# ComputeCalculator.net
KiCad netlist of a schematic drawn in EAGLE
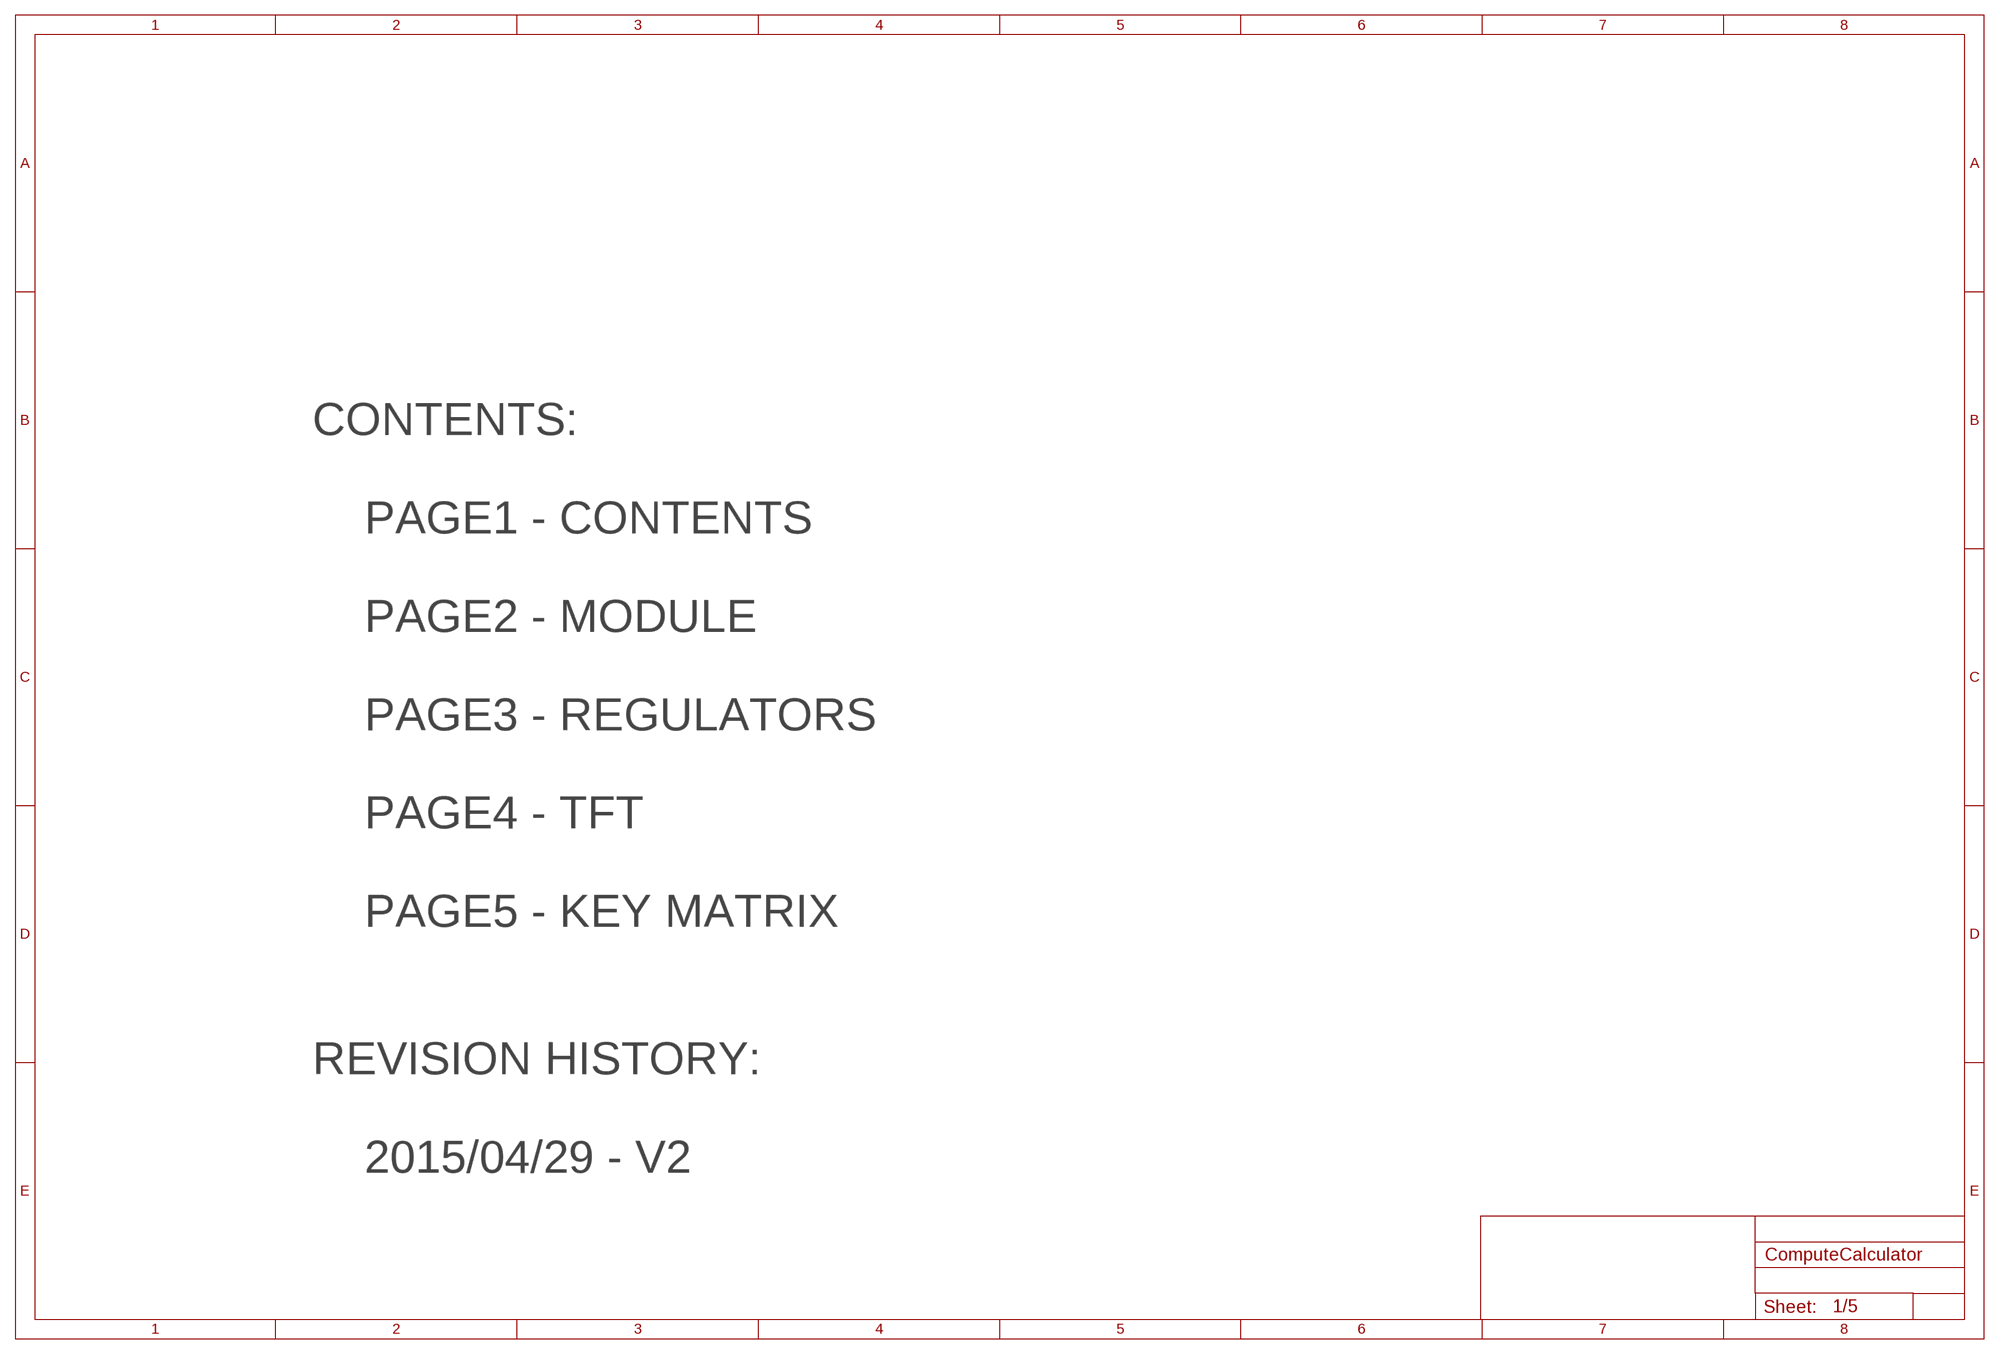
[diagram p0: schematic, sheet 1]
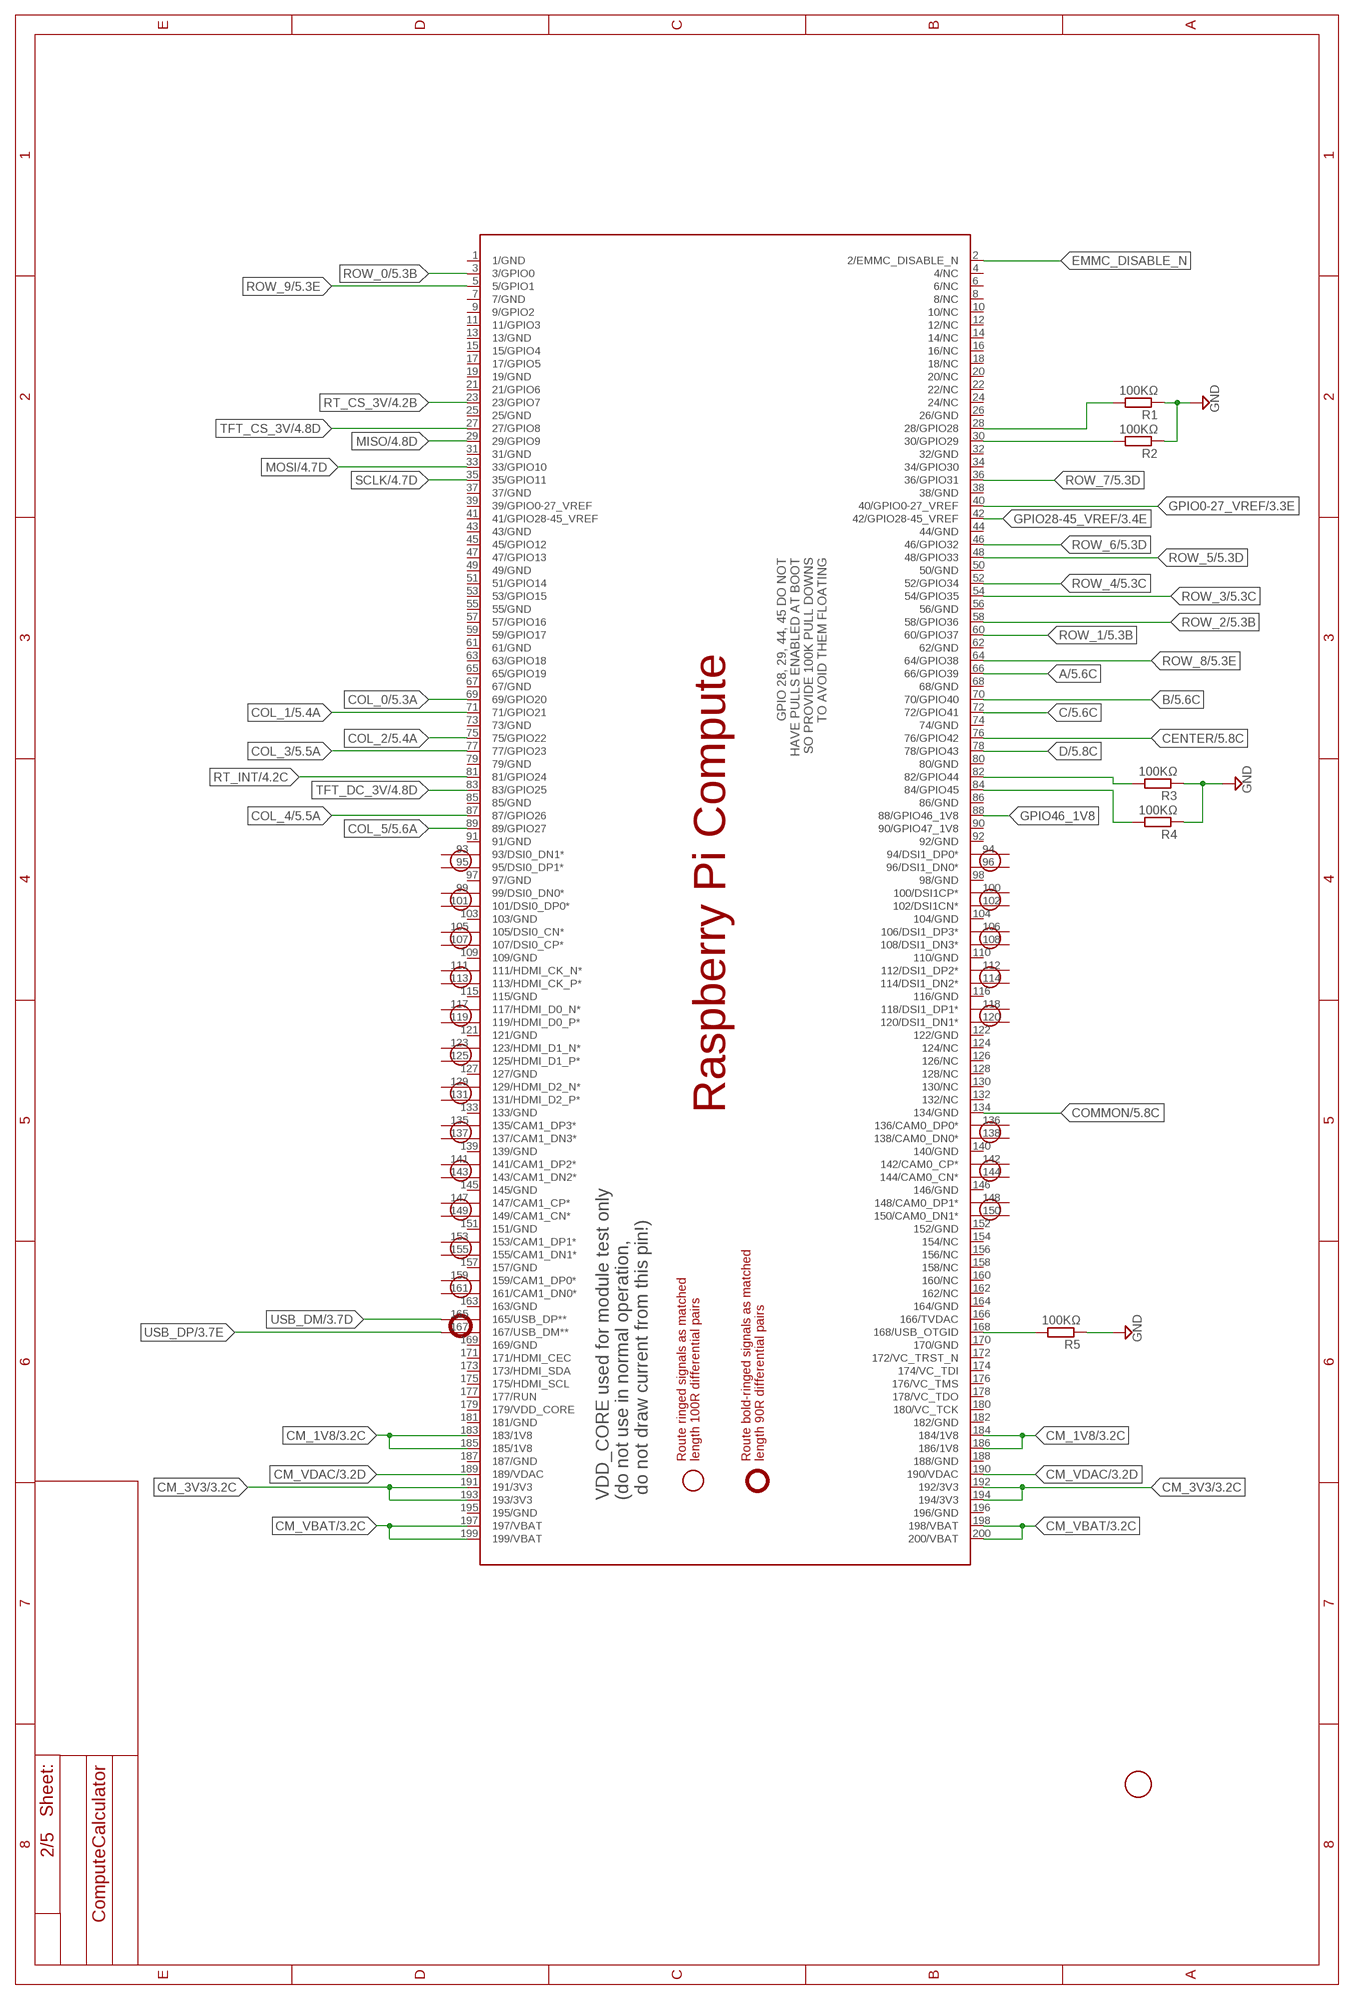
[diagram p1: schematic, sheet 2]
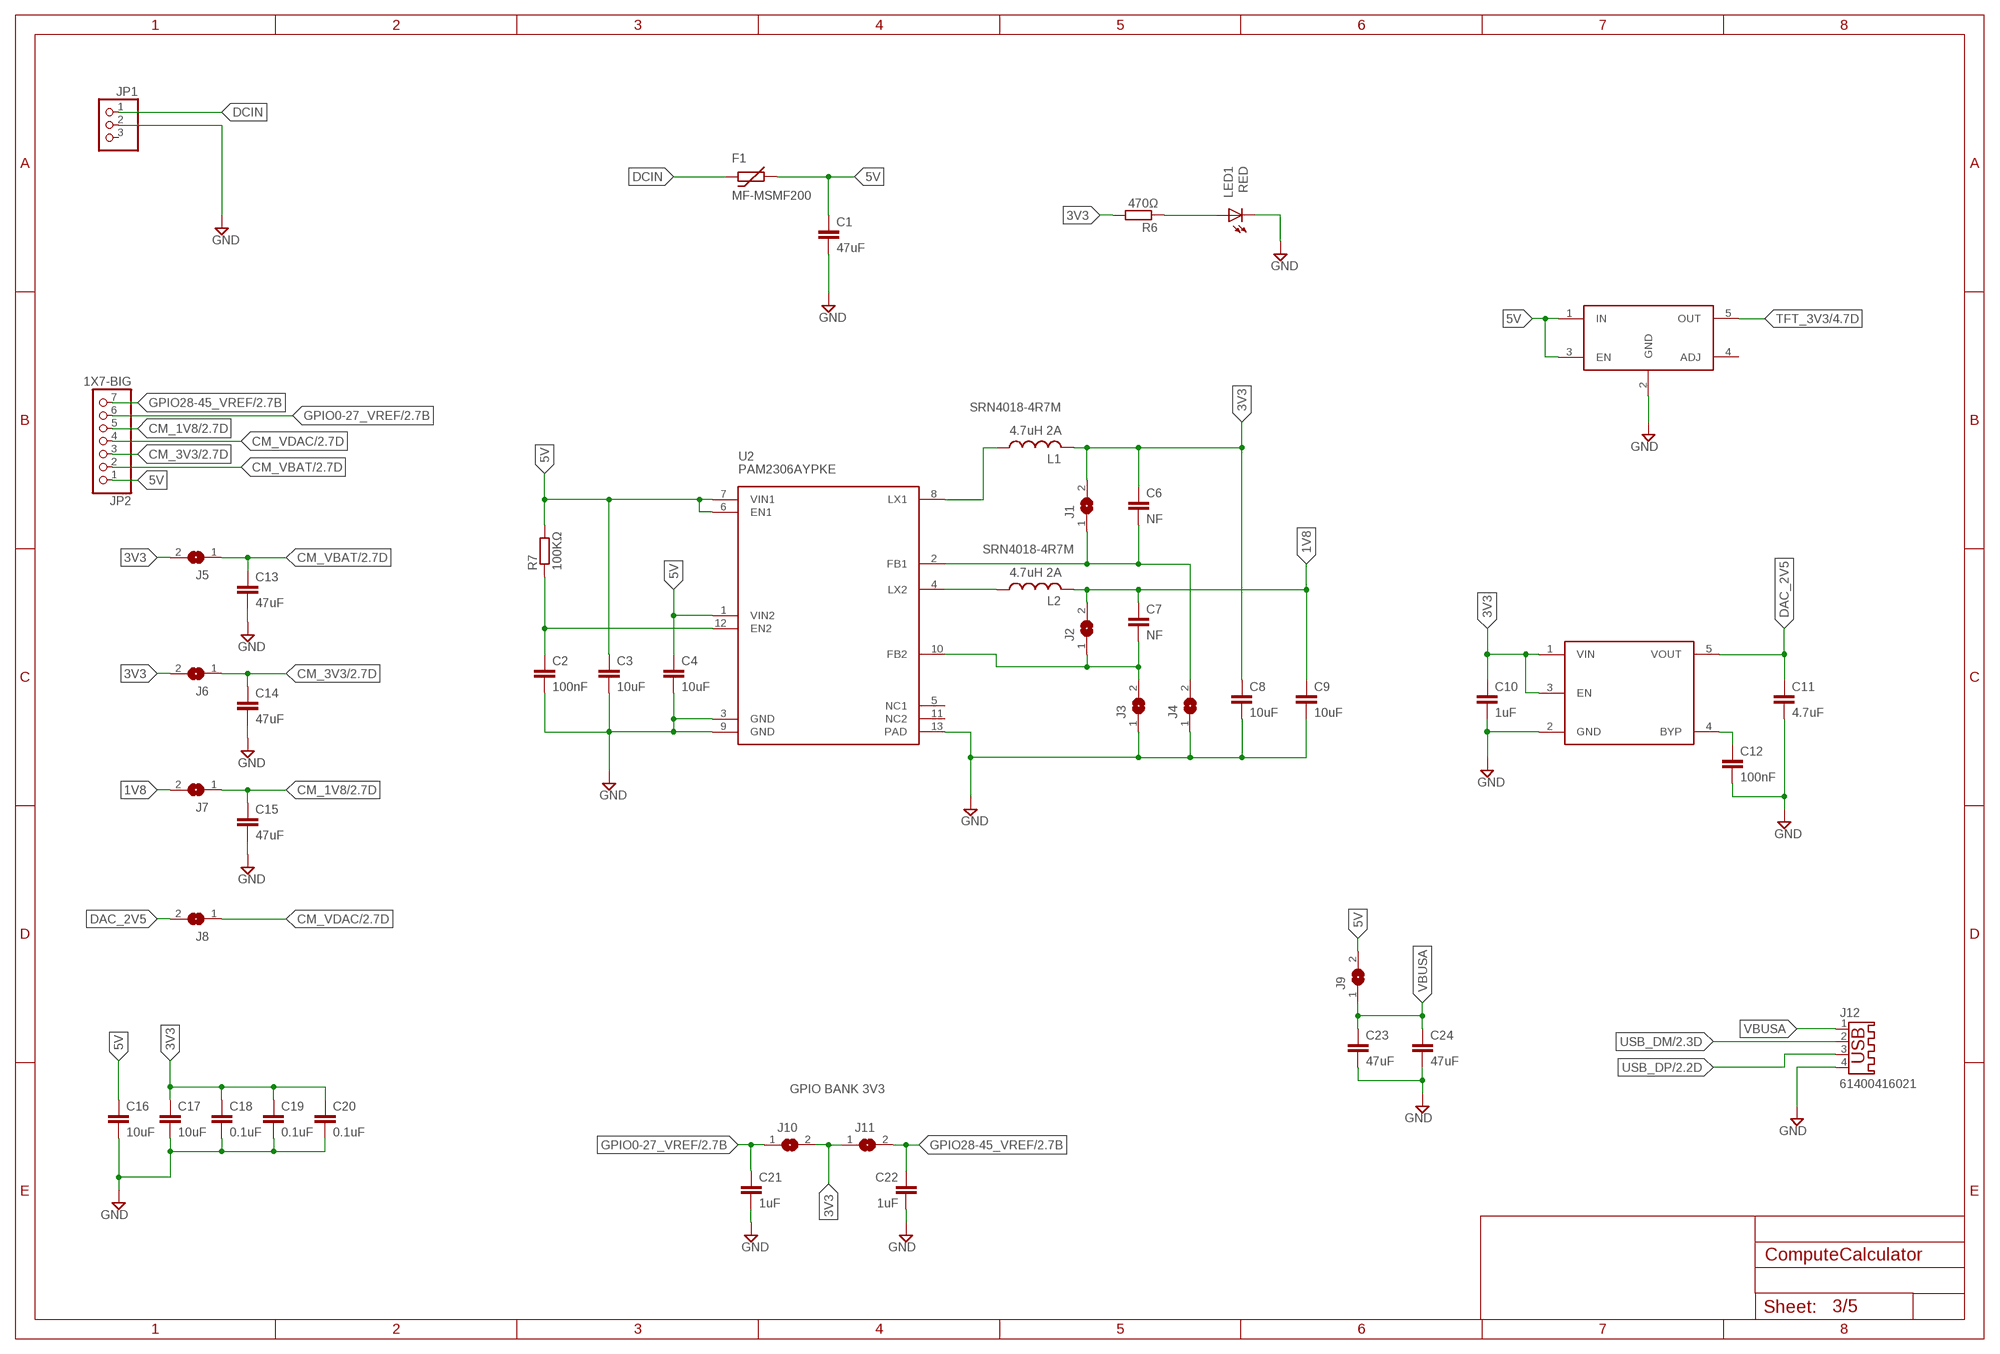
[diagram p2: schematic, sheet 3]
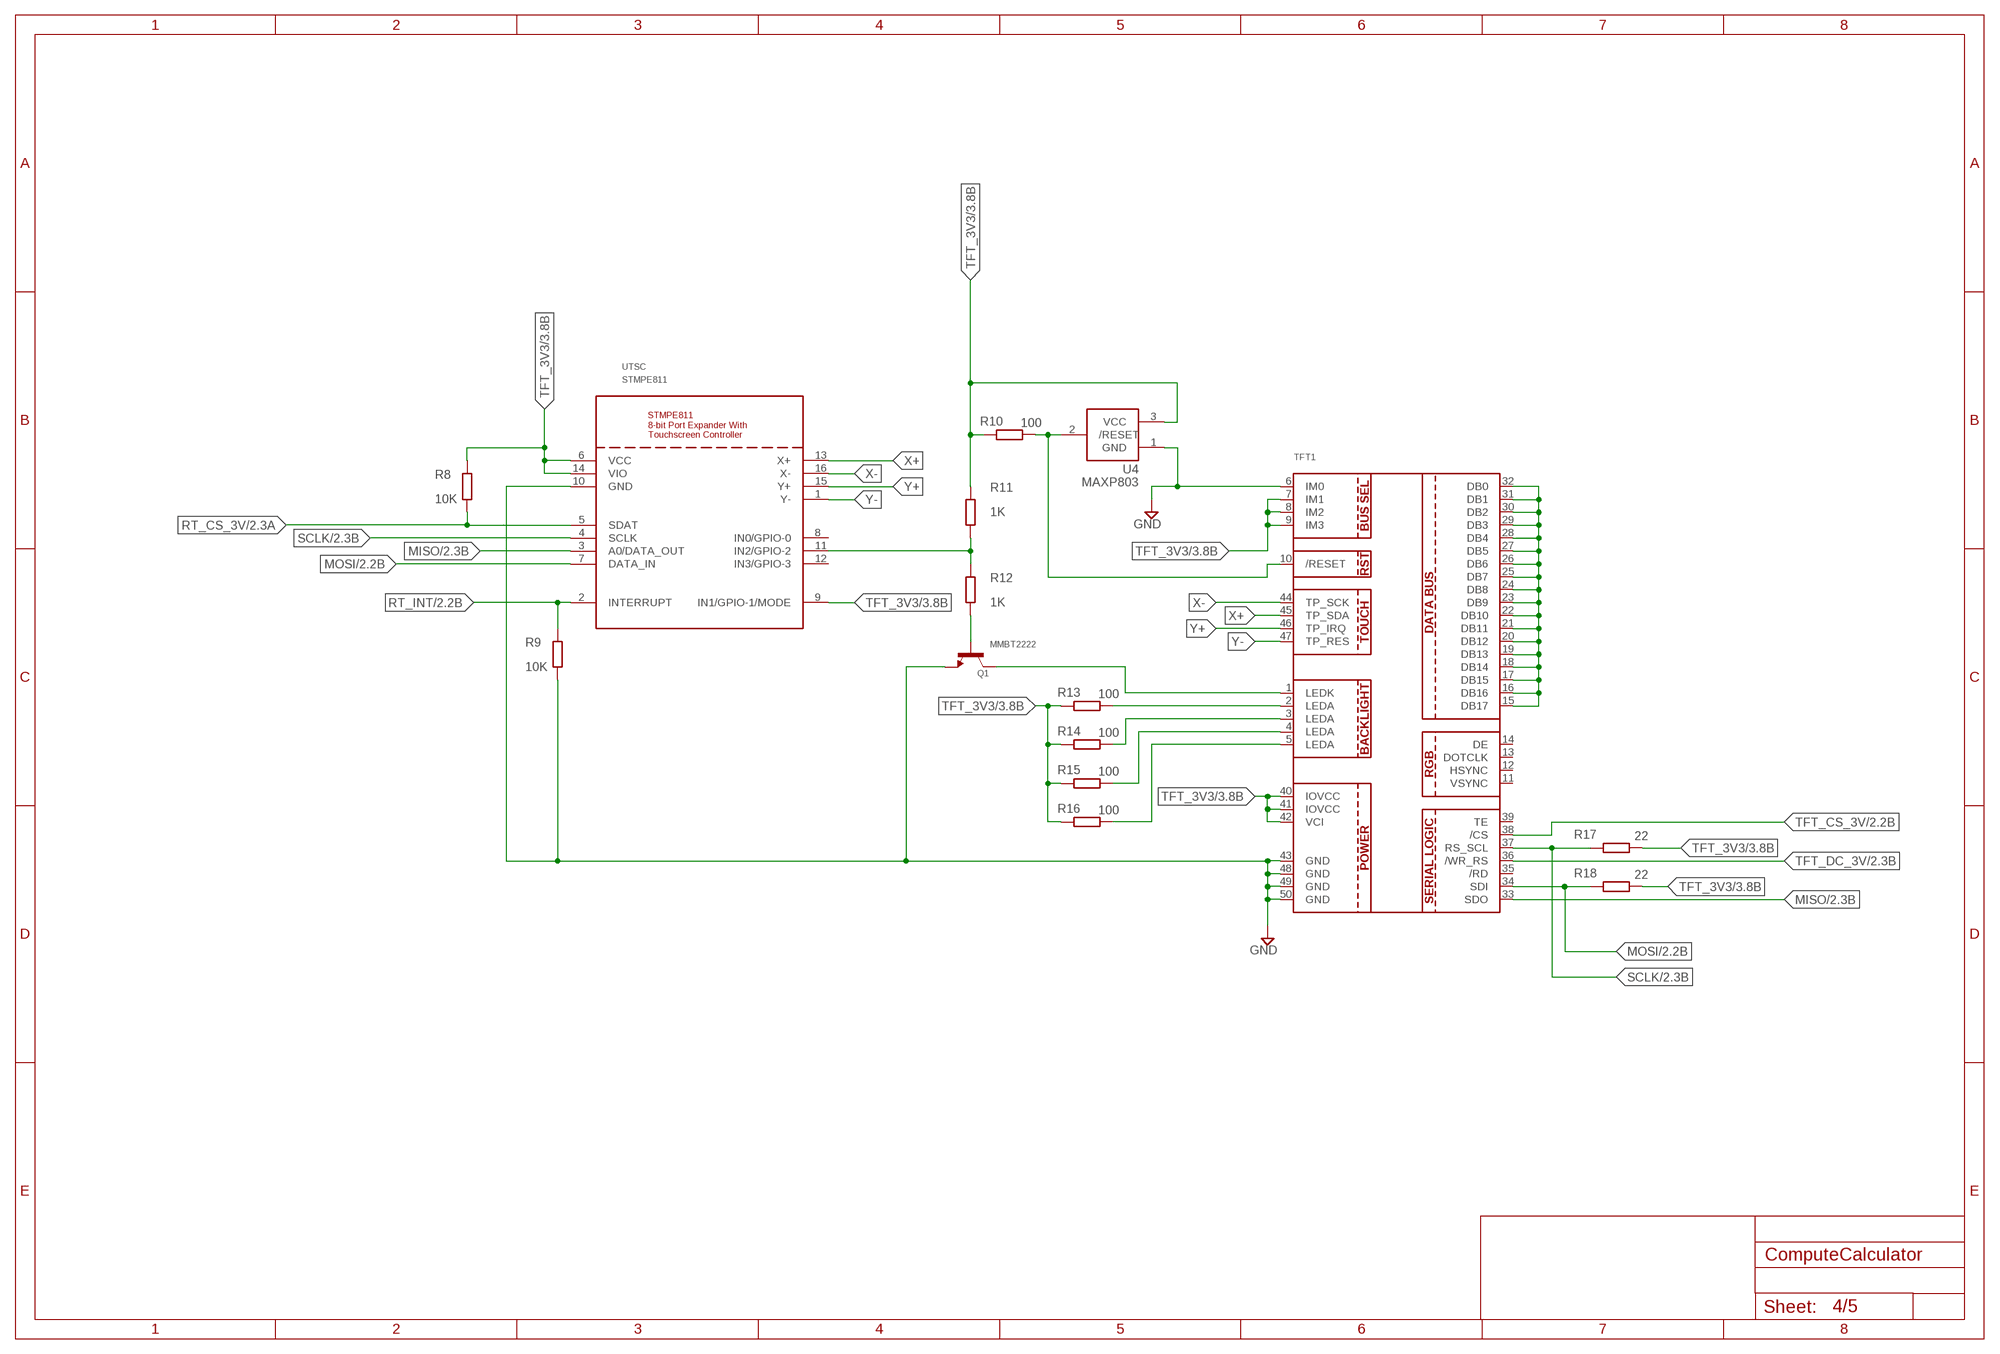
[diagram p3: schematic, sheet 4]
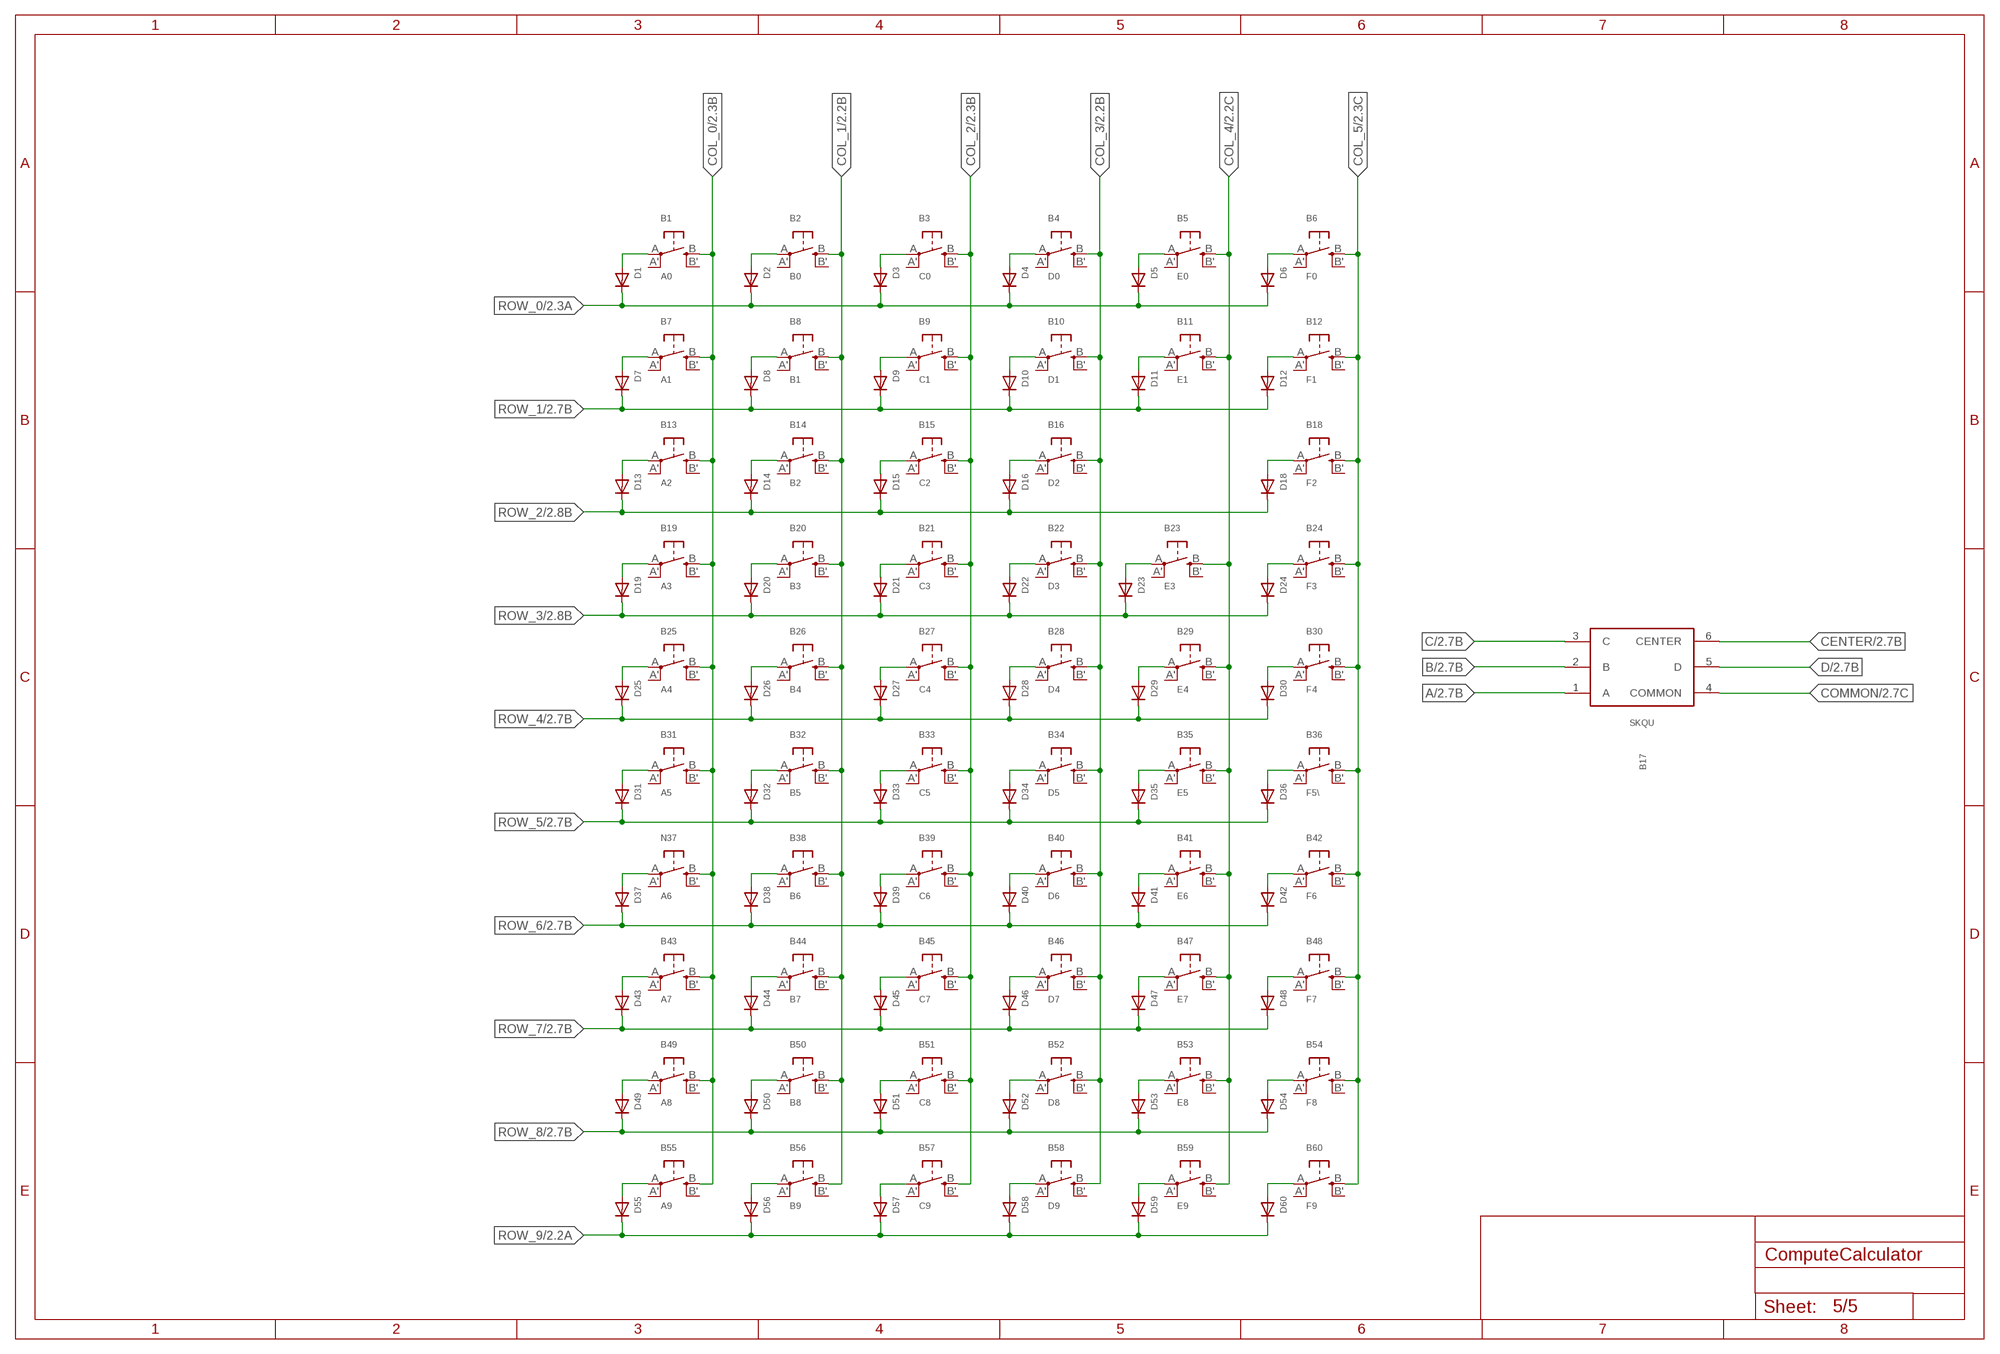
[diagram p4: schematic, sheet 5]

(export (version "E")
  (design (tool "Eeschema 10.0.6"))
  (components
    (comp (ref "C1")
      (value "47uF")
      (footprint "eagle-import:C0603")
      (libsource (lib "eagle-import") (part "CAPACITOR"))
    )
    (comp (ref "C2")
      (value "100nF")
      (footprint "eagle-import:C1206")
      (libsource (lib "eagle-import") (part "C-EUC1206"))
    )
    (comp (ref "C3")
      (value "10uF")
      (footprint "eagle-import:C1206")
      (libsource (lib "eagle-import") (part "C-EUC1206"))
    )
    (comp (ref "C4")
      (value "10uF")
      (footprint "eagle-import:C1206")
      (libsource (lib "eagle-import") (part "C-EUC1206"))
    )
    (comp (ref "C6")
      (value "NF")
      (footprint "eagle-import:C1206")
      (libsource (lib "eagle-import") (part "C-EUC1206"))
    )
    (comp (ref "C7")
      (value "NF")
      (footprint "eagle-import:C1206")
      (libsource (lib "eagle-import") (part "C-EUC1206"))
    )
    (comp (ref "C8")
      (value "10uF")
      (footprint "eagle-import:C1206")
      (libsource (lib "eagle-import") (part "C-EUC1206"))
    )
    (comp (ref "C9")
      (value "10uF")
      (footprint "eagle-import:C1206")
      (libsource (lib "eagle-import") (part "C-EUC1206"))
    )
    (comp (ref "C10")
      (value "1uF")
      (footprint "eagle-import:C1206")
      (libsource (lib "eagle-import") (part "C-EUC1206"))
    )
    (comp (ref "C11")
      (value "4.7uF")
      (footprint "eagle-import:C1206")
      (libsource (lib "eagle-import") (part "C-EUC1206"))
    )
    (comp (ref "C12")
      (value "100nF")
      (footprint "eagle-import:C1206")
      (libsource (lib "eagle-import") (part "C-EUC1206"))
    )
    (comp (ref "C13")
      (value "47uF")
      (footprint "eagle-import:C1206")
      (libsource (lib "eagle-import") (part "C-EUC1206"))
    )
    (comp (ref "C14")
      (value "47uF")
      (footprint "eagle-import:C1206")
      (libsource (lib "eagle-import") (part "C-EUC1206"))
    )
    (comp (ref "C15")
      (value "47uF")
      (footprint "eagle-import:C1206")
      (libsource (lib "eagle-import") (part "C-EUC1206"))
    )
    (comp (ref "C16")
      (value "10uF")
      (footprint "eagle-import:C1206")
      (libsource (lib "eagle-import") (part "C-EUC1206"))
    )
    (comp (ref "C17")
      (value "10uF")
      (footprint "eagle-import:C1206")
      (libsource (lib "eagle-import") (part "C-EUC1206"))
    )
    (comp (ref "C18")
      (value "0.1uF")
      (footprint "eagle-import:C1206")
      (libsource (lib "eagle-import") (part "C-EUC1206"))
    )
    (comp (ref "C19")
      (value "0.1uF")
      (footprint "eagle-import:C1206")
      (libsource (lib "eagle-import") (part "C-EUC1206"))
    )
    (comp (ref "C20")
      (value "0.1uF")
      (footprint "eagle-import:C1206")
      (libsource (lib "eagle-import") (part "C-EUC1206"))
    )
    (comp (ref "C21")
      (value "1uF")
      (footprint "eagle-import:C1206")
      (libsource (lib "eagle-import") (part "C-EUC1206"))
    )
    (comp (ref "C22")
      (value "1uF")
      (footprint "eagle-import:C1206")
      (libsource (lib "eagle-import") (part "C-EUC1206"))
    )
    (comp (ref "C23")
      (value "47uF")
      (footprint "eagle-import:C1206")
      (libsource (lib "eagle-import") (part "C-EUC1206"))
    )
    (comp (ref "C24")
      (value "47uF")
      (footprint "eagle-import:C1206")
      (libsource (lib "eagle-import") (part "C-EUC1206"))
    )
    (comp (ref "F1")
      (value "MF-MSMF200")
      (footprint "eagle-import:MF-MSMF200")
      (libsource (lib "eagle-import") (part "MF-MSMF200"))
    )
    (comp (ref "J1")
      (value "JUMPER")
      (footprint "eagle-import:SJW")
      (libsource (lib "eagle-import") (part "JUMPER"))
    )
    (comp (ref "J2")
      (value "JUMPER")
      (footprint "eagle-import:SJW")
      (libsource (lib "eagle-import") (part "JUMPER"))
    )
    (comp (ref "J3")
      (value "JUMPER")
      (footprint "eagle-import:SJW")
      (libsource (lib "eagle-import") (part "JUMPER"))
    )
    (comp (ref "J4")
      (value "JUMPER")
      (footprint "eagle-import:SJW")
      (libsource (lib "eagle-import") (part "JUMPER"))
    )
    (comp (ref "J5")
      (value "JUMPER")
      (footprint "eagle-import:SJW")
      (libsource (lib "eagle-import") (part "JUMPER"))
    )
    (comp (ref "J6")
      (value "JUMPER")
      (footprint "eagle-import:SJW")
      (libsource (lib "eagle-import") (part "JUMPER"))
    )
    (comp (ref "J7")
      (value "JUMPER")
      (footprint "eagle-import:SJW")
      (libsource (lib "eagle-import") (part "JUMPER"))
    )
    (comp (ref "J8")
      (value "JUMPER")
      (footprint "eagle-import:SJW")
      (libsource (lib "eagle-import") (part "JUMPER"))
    )
    (comp (ref "J9")
      (value "JUMPER")
      (footprint "eagle-import:SJW")
      (libsource (lib "eagle-import") (part "JUMPER"))
    )
    (comp (ref "J10")
      (value "JUMPER")
      (footprint "eagle-import:SJW")
      (libsource (lib "eagle-import") (part "JUMPER"))
    )
    (comp (ref "J11")
      (value "JUMPER")
      (footprint "eagle-import:SJW")
      (libsource (lib "eagle-import") (part "JUMPER"))
    )
    (comp (ref "J12")
      (value "61400416021")
      (footprint "eagle-import:USB-A003")
      (libsource (lib "eagle-import") (part "USB-A003"))
    )
    (comp (ref "JP1")
      (value "PINHD-1X3")
      (footprint "eagle-import:1X03")
      (libsource (lib "eagle-import") (part "PINHD-1X3"))
    )
    (comp (ref "JP2")
      (value "1X7-BIG")
      (footprint "eagle-import:1X7-BIG")
      (libsource (lib "eagle-import") (part "1X7-BIG"))
    )
    (comp (ref "L1")
      (value "SRN4018-4R7M")
      (footprint "eagle-import:POWER-CHOKE_WE-TPC")
      (libsource (lib "eagle-import") (part "L-USWE-TPC"))
    )
    (comp (ref "L2")
      (value "SRN4018-4R7M")
      (footprint "eagle-import:POWER-CHOKE_WE-TPC")
      (libsource (lib "eagle-import") (part "L-USWE-TPC"))
    )
    (comp (ref "LED1")
      (value "RED")
      (footprint "eagle-import:CHIP-LED0805")
      (libsource (lib "eagle-import") (part "LEDCHIP-LED0805"))
    )
    (comp (ref "R6")
      (value "470Ω")
      (footprint "eagle-import:M1206")
      (libsource (lib "eagle-import") (part "R-EU_M1206"))
    )
    (comp (ref "R7")
      (value "100KΩ")
      (footprint "eagle-import:M1206")
      (libsource (lib "eagle-import") (part "R-EU_M1206"))
    )
    (comp (ref "U1")
      (value "MIC5225")
      (footprint "eagle-import:SOT-25")
      (libsource (lib "eagle-import") (part "MIC5225"))
    )
    (comp (ref "U2")
      (value "PAM2306AYPKE")
      (footprint "eagle-import:WDFN_12L")
      (libsource (lib "eagle-import") (part "PAM2306AYPKE"))
    )
    (comp (ref "U3")
      (value "AP7115-25SEG")
      (footprint "eagle-import:SOT-25")
      (libsource (lib "eagle-import") (part "AP7115-25SEG"))
    )
    (comp (ref "Q1")
      (value "MMBT2222")
      (footprint "eagle-import:SOT23-WIDE")
      (libsource (lib "eagle-import") (part "TRANSISTOR_NPNWIDE"))
    )
    (comp (ref "R8")
      (value "10K")
      (footprint "eagle-import:M1206")
      (libsource (lib "eagle-import") (part "R-EU_M1206"))
    )
    (comp (ref "R9")
      (value "10K")
      (footprint "eagle-import:M1206")
      (libsource (lib "eagle-import") (part "R-EU_M1206"))
    )
    (comp (ref "R10")
      (value "100")
      (footprint "eagle-import:M1206")
      (libsource (lib "eagle-import") (part "R-EU_M1206"))
    )
    (comp (ref "R11")
      (value "1K")
      (footprint "eagle-import:M1206")
      (libsource (lib "eagle-import") (part "R-EU_M1206"))
    )
    (comp (ref "R12")
      (value "1K")
      (footprint "eagle-import:M1206")
      (libsource (lib "eagle-import") (part "R-EU_M1206"))
    )
    (comp (ref "R13")
      (value "100")
      (footprint "eagle-import:M1206")
      (libsource (lib "eagle-import") (part "R-EU_M1206"))
    )
    (comp (ref "R14")
      (value "100")
      (footprint "eagle-import:M1206")
      (libsource (lib "eagle-import") (part "R-EU_M1206"))
    )
    (comp (ref "R15")
      (value "100")
      (footprint "eagle-import:M1206")
      (libsource (lib "eagle-import") (part "R-EU_M1206"))
    )
    (comp (ref "R16")
      (value "100")
      (footprint "eagle-import:M1206")
      (libsource (lib "eagle-import") (part "R-EU_M1206"))
    )
    (comp (ref "R17")
      (value "22")
      (footprint "eagle-import:M1206")
      (libsource (lib "eagle-import") (part "R-EU_M1206"))
    )
    (comp (ref "R18")
      (value "22")
      (footprint "eagle-import:M1206")
      (libsource (lib "eagle-import") (part "R-EU_M1206"))
    )
    (comp (ref "TFT1")
      (value "DISP_LCD_CTP28_DATASHEET")
      (footprint "eagle-import:TFT_CTP28")
      (libsource (lib "eagle-import") (part "DISP_LCD_CTP28_DATASHEET"))
    )
    (comp (ref "U4")
      (value "MAXP803")
      (footprint "eagle-import:SOT23")
      (libsource (lib "eagle-import") (part "AXP083-SAG"))
    )
    (comp (ref "UTSC")
      (value "STMPE811")
      (footprint "eagle-import:QFN16L")
      (libsource (lib "eagle-import") (part "STMPE811"))
    )
    (comp (ref "$$PCB100")
      (value "RPI_COMPUTE")
      (footprint "eagle-import:RPI_COMPUTE")
      (libsource (lib "eagle-import") (part "RPI_COMPUTE"))
    )
    (comp (ref "$$U$1")
      (value "FIDUCIAL")
      (footprint "eagle-import:FIDUCIAL_1MM")
      (libsource (lib "eagle-import") (part "FIDUCIAL"))
    )
    (comp (ref "R1")
      (value "100KΩ")
      (footprint "eagle-import:M1206")
      (libsource (lib "eagle-import") (part "R-EU_M1206"))
    )
    (comp (ref "R2")
      (value "100KΩ")
      (footprint "eagle-import:M1206")
      (libsource (lib "eagle-import") (part "R-EU_M1206"))
    )
    (comp (ref "R3")
      (value "100KΩ")
      (footprint "eagle-import:M1206")
      (libsource (lib "eagle-import") (part "R-EU_M1206"))
    )
    (comp (ref "R4")
      (value "100KΩ")
      (footprint "eagle-import:M1206")
      (libsource (lib "eagle-import") (part "R-EU_M1206"))
    )
    (comp (ref "R5")
      (value "100KΩ")
      (footprint "eagle-import:M1206")
      (libsource (lib "eagle-import") (part "R-EU_M1206"))
    )
    (comp (ref "B1")
      (value "A0")
      (footprint "eagle-import:EVQ-Q2")
      (libsource (lib "eagle-import") (part "SWITCH_TACT_SMT"))
    )
    (comp (ref "B2")
      (value "B0")
      (footprint "eagle-import:EVQ-Q2")
      (libsource (lib "eagle-import") (part "SWITCH_TACT_SMT"))
    )
    (comp (ref "B3")
      (value "C0")
      (footprint "eagle-import:EVQ-Q2")
      (libsource (lib "eagle-import") (part "SWITCH_TACT_SMT"))
    )
    (comp (ref "B4")
      (value "D0")
      (footprint "eagle-import:EVQ-Q2")
      (libsource (lib "eagle-import") (part "SWITCH_TACT_SMT"))
    )
    (comp (ref "B5")
      (value "E0")
      (footprint "eagle-import:EVQ-Q2")
      (libsource (lib "eagle-import") (part "SWITCH_TACT_SMT"))
    )
    (comp (ref "B6")
      (value "F0")
      (footprint "eagle-import:EVQ-Q2")
      (libsource (lib "eagle-import") (part "SWITCH_TACT_SMT"))
    )
    (comp (ref "B7")
      (value "A1")
      (footprint "eagle-import:EVQ-Q2")
      (libsource (lib "eagle-import") (part "SWITCH_TACT_SMT"))
    )
    (comp (ref "B8")
      (value "B1")
      (footprint "eagle-import:EVQ-Q2")
      (libsource (lib "eagle-import") (part "SWITCH_TACT_SMT"))
    )
    (comp (ref "B9")
      (value "C1")
      (footprint "eagle-import:EVQ-Q2")
      (libsource (lib "eagle-import") (part "SWITCH_TACT_SMT"))
    )
    (comp (ref "B10")
      (value "D1")
      (footprint "eagle-import:EVQ-Q2")
      (libsource (lib "eagle-import") (part "SWITCH_TACT_SMT"))
    )
    (comp (ref "B11")
      (value "E1")
      (footprint "eagle-import:EVQ-Q2")
      (libsource (lib "eagle-import") (part "SWITCH_TACT_SMT"))
    )
    (comp (ref "B12")
      (value "F1")
      (footprint "eagle-import:EVQ-Q2")
      (libsource (lib "eagle-import") (part "SWITCH_TACT_SMT"))
    )
    (comp (ref "B13")
      (value "A2")
      (footprint "eagle-import:EVQ-Q2")
      (libsource (lib "eagle-import") (part "SWITCH_TACT_SMT"))
    )
    (comp (ref "B14")
      (value "B2")
      (footprint "eagle-import:EVQ-Q2")
      (libsource (lib "eagle-import") (part "SWITCH_TACT_SMT"))
    )
    (comp (ref "B15")
      (value "C2")
      (footprint "eagle-import:EVQ-Q2")
      (libsource (lib "eagle-import") (part "SWITCH_TACT_SMT"))
    )
    (comp (ref "B16")
      (value "D2")
      (footprint "eagle-import:EVQ-Q2")
      (libsource (lib "eagle-import") (part "SWITCH_TACT_SMT"))
    )
    (comp (ref "B17")
      (value "SKQU")
      (footprint "eagle-import:SKQU")
      (libsource (lib "eagle-import") (part "SKQU"))
    )
    (comp (ref "B18")
      (value "F2")
      (footprint "eagle-import:EVQ-Q2")
      (libsource (lib "eagle-import") (part "SWITCH_TACT_SMT"))
    )
    (comp (ref "B19")
      (value "A3")
      (footprint "eagle-import:EVQ-Q2")
      (libsource (lib "eagle-import") (part "SWITCH_TACT_SMT"))
    )
    (comp (ref "B20")
      (value "B3")
      (footprint "eagle-import:EVQ-Q2")
      (libsource (lib "eagle-import") (part "SWITCH_TACT_SMT"))
    )
    (comp (ref "B21")
      (value "C3")
      (footprint "eagle-import:EVQ-Q2")
      (libsource (lib "eagle-import") (part "SWITCH_TACT_SMT"))
    )
    (comp (ref "B22")
      (value "D3")
      (footprint "eagle-import:EVQ-Q2")
      (libsource (lib "eagle-import") (part "SWITCH_TACT_SMT"))
    )
    (comp (ref "B23")
      (value "E3")
      (footprint "eagle-import:EVQ-Q2")
      (libsource (lib "eagle-import") (part "SWITCH_TACT_SMT"))
    )
    (comp (ref "B24")
      (value "F3")
      (footprint "eagle-import:EVQ-Q2")
      (libsource (lib "eagle-import") (part "SWITCH_TACT_SMT"))
    )
    (comp (ref "B25")
      (value "A4")
      (footprint "eagle-import:EVQ-Q2")
      (libsource (lib "eagle-import") (part "SWITCH_TACT_SMT"))
    )
    (comp (ref "B26")
      (value "B4")
      (footprint "eagle-import:EVQ-Q2")
      (libsource (lib "eagle-import") (part "SWITCH_TACT_SMT"))
    )
    (comp (ref "B27")
      (value "C4")
      (footprint "eagle-import:EVQ-Q2")
      (libsource (lib "eagle-import") (part "SWITCH_TACT_SMT"))
    )
    (comp (ref "B28")
      (value "D4")
      (footprint "eagle-import:EVQ-Q2")
      (libsource (lib "eagle-import") (part "SWITCH_TACT_SMT"))
    )
    (comp (ref "B29")
      (value "E4")
      (footprint "eagle-import:EVQ-Q2")
      (libsource (lib "eagle-import") (part "SWITCH_TACT_SMT"))
    )
    (comp (ref "B30")
      (value "F4")
      (footprint "eagle-import:EVQ-Q2")
      (libsource (lib "eagle-import") (part "SWITCH_TACT_SMT"))
    )
    (comp (ref "B31")
      (value "A5")
      (footprint "eagle-import:EVQ-Q2")
      (libsource (lib "eagle-import") (part "SWITCH_TACT_SMT"))
    )
    (comp (ref "B32")
      (value "B5")
      (footprint "eagle-import:EVQ-Q2")
      (libsource (lib "eagle-import") (part "SWITCH_TACT_SMT"))
    )
    (comp (ref "B33")
      (value "C5")
      (footprint "eagle-import:EVQ-Q2")
      (libsource (lib "eagle-import") (part "SWITCH_TACT_SMT"))
    )
    (comp (ref "B34")
      (value "D5")
      (footprint "eagle-import:EVQ-Q2")
      (libsource (lib "eagle-import") (part "SWITCH_TACT_SMT"))
    )
    (comp (ref "B35")
      (value "E5")
      (footprint "eagle-import:EVQ-Q2")
      (libsource (lib "eagle-import") (part "SWITCH_TACT_SMT"))
    )
    (comp (ref "B36")
      (value "F5\\")
      (footprint "eagle-import:EVQ-Q2")
      (libsource (lib "eagle-import") (part "SWITCH_TACT_SMT"))
    )
    (comp (ref "B38")
      (value "B6")
      (footprint "eagle-import:EVQ-Q2")
      (libsource (lib "eagle-import") (part "SWITCH_TACT_SMT"))
    )
    (comp (ref "B39")
      (value "C6")
      (footprint "eagle-import:EVQ-Q2")
      (libsource (lib "eagle-import") (part "SWITCH_TACT_SMT"))
    )
    (comp (ref "B40")
      (value "D6")
      (footprint "eagle-import:EVQ-Q2")
      (libsource (lib "eagle-import") (part "SWITCH_TACT_SMT"))
    )
    (comp (ref "B41")
      (value "E6")
      (footprint "eagle-import:EVQ-Q2")
      (libsource (lib "eagle-import") (part "SWITCH_TACT_SMT"))
    )
    (comp (ref "B42")
      (value "F6")
      (footprint "eagle-import:EVQ-Q2")
      (libsource (lib "eagle-import") (part "SWITCH_TACT_SMT"))
    )
    (comp (ref "B43")
      (value "A7")
      (footprint "eagle-import:EVQ-Q2")
      (libsource (lib "eagle-import") (part "SWITCH_TACT_SMT"))
    )
    (comp (ref "B44")
      (value "B7")
      (footprint "eagle-import:EVQ-Q2")
      (libsource (lib "eagle-import") (part "SWITCH_TACT_SMT"))
    )
    (comp (ref "B45")
      (value "C7")
      (footprint "eagle-import:EVQ-Q2")
      (libsource (lib "eagle-import") (part "SWITCH_TACT_SMT"))
    )
    (comp (ref "B46")
      (value "D7")
      (footprint "eagle-import:EVQ-Q2")
      (libsource (lib "eagle-import") (part "SWITCH_TACT_SMT"))
    )
    (comp (ref "B47")
      (value "E7")
      (footprint "eagle-import:EVQ-Q2")
      (libsource (lib "eagle-import") (part "SWITCH_TACT_SMT"))
    )
    (comp (ref "B48")
      (value "F7")
      (footprint "eagle-import:EVQ-Q2")
      (libsource (lib "eagle-import") (part "SWITCH_TACT_SMT"))
    )
    (comp (ref "B49")
      (value "A8")
      (footprint "eagle-import:EVQ-Q2")
      (libsource (lib "eagle-import") (part "SWITCH_TACT_SMT"))
    )
    (comp (ref "B50")
      (value "B8")
      (footprint "eagle-import:EVQ-Q2")
      (libsource (lib "eagle-import") (part "SWITCH_TACT_SMT"))
    )
    (comp (ref "B51")
      (value "C8")
      (footprint "eagle-import:EVQ-Q2")
      (libsource (lib "eagle-import") (part "SWITCH_TACT_SMT"))
    )
    (comp (ref "B52")
      (value "D8")
      (footprint "eagle-import:EVQ-Q2")
      (libsource (lib "eagle-import") (part "SWITCH_TACT_SMT"))
    )
    (comp (ref "B53")
      (value "E8")
      (footprint "eagle-import:EVQ-Q2")
      (libsource (lib "eagle-import") (part "SWITCH_TACT_SMT"))
    )
    (comp (ref "B54")
      (value "F8")
      (footprint "eagle-import:EVQ-Q2")
      (libsource (lib "eagle-import") (part "SWITCH_TACT_SMT"))
    )
    (comp (ref "B55")
      (value "A9")
      (footprint "eagle-import:EVQ-Q2")
      (libsource (lib "eagle-import") (part "SWITCH_TACT_SMT"))
    )
    (comp (ref "B56")
      (value "B9")
      (footprint "eagle-import:EVQ-Q2")
      (libsource (lib "eagle-import") (part "SWITCH_TACT_SMT"))
    )
    (comp (ref "B57")
      (value "C9")
      (footprint "eagle-import:EVQ-Q2")
      (libsource (lib "eagle-import") (part "SWITCH_TACT_SMT"))
    )
    (comp (ref "B58")
      (value "D9")
      (footprint "eagle-import:EVQ-Q2")
      (libsource (lib "eagle-import") (part "SWITCH_TACT_SMT"))
    )
    (comp (ref "B59")
      (value "E9")
      (footprint "eagle-import:EVQ-Q2")
      (libsource (lib "eagle-import") (part "SWITCH_TACT_SMT"))
    )
    (comp (ref "B60")
      (value "F9")
      (footprint "eagle-import:EVQ-Q2")
      (libsource (lib "eagle-import") (part "SWITCH_TACT_SMT"))
    )
    (comp (ref "D1")
      (value "DIODESMA")
      (footprint "eagle-import:SMADIODE")
      (libsource (lib "eagle-import") (part "DIODESMA"))
    )
    (comp (ref "D2")
      (value "DIODESMA")
      (footprint "eagle-import:SMADIODE")
      (libsource (lib "eagle-import") (part "DIODESMA"))
    )
    (comp (ref "D3")
      (value "DIODESMA")
      (footprint "eagle-import:SMADIODE")
      (libsource (lib "eagle-import") (part "DIODESMA"))
    )
    (comp (ref "D4")
      (value "DIODESMA")
      (footprint "eagle-import:SMADIODE")
      (libsource (lib "eagle-import") (part "DIODESMA"))
    )
    (comp (ref "D5")
      (value "DIODESMA")
      (footprint "eagle-import:SMADIODE")
      (libsource (lib "eagle-import") (part "DIODESMA"))
    )
    (comp (ref "D6")
      (value "DIODESMA")
      (footprint "eagle-import:SMADIODE")
      (libsource (lib "eagle-import") (part "DIODESMA"))
    )
    (comp (ref "D7")
      (value "DIODESMA")
      (footprint "eagle-import:SMADIODE")
      (libsource (lib "eagle-import") (part "DIODESMA"))
    )
    (comp (ref "D8")
      (value "DIODESMA")
      (footprint "eagle-import:SMADIODE")
      (libsource (lib "eagle-import") (part "DIODESMA"))
    )
    (comp (ref "D9")
      (value "DIODESMA")
      (footprint "eagle-import:SMADIODE")
      (libsource (lib "eagle-import") (part "DIODESMA"))
    )
    (comp (ref "D10")
      (value "DIODESMA")
      (footprint "eagle-import:SMADIODE")
      (libsource (lib "eagle-import") (part "DIODESMA"))
    )
    (comp (ref "D11")
      (value "DIODESMA")
      (footprint "eagle-import:SMADIODE")
      (libsource (lib "eagle-import") (part "DIODESMA"))
    )
    (comp (ref "D12")
      (value "DIODESMA")
      (footprint "eagle-import:SMADIODE")
      (libsource (lib "eagle-import") (part "DIODESMA"))
    )
    (comp (ref "D13")
      (value "DIODESMA")
      (footprint "eagle-import:SMADIODE")
      (libsource (lib "eagle-import") (part "DIODESMA"))
    )
    (comp (ref "D14")
      (value "DIODESMA")
      (footprint "eagle-import:SMADIODE")
      (libsource (lib "eagle-import") (part "DIODESMA"))
    )
    (comp (ref "D15")
      (value "DIODESMA")
      (footprint "eagle-import:SMADIODE")
      (libsource (lib "eagle-import") (part "DIODESMA"))
    )
    (comp (ref "D16")
      (value "DIODESMA")
      (footprint "eagle-import:SMADIODE")
      (libsource (lib "eagle-import") (part "DIODESMA"))
    )
    (comp (ref "D18")
      (value "DIODESMA")
      (footprint "eagle-import:SMADIODE")
      (libsource (lib "eagle-import") (part "DIODESMA"))
    )
    (comp (ref "D19")
      (value "DIODESMA")
      (footprint "eagle-import:SMADIODE")
      (libsource (lib "eagle-import") (part "DIODESMA"))
    )
    (comp (ref "D20")
      (value "DIODESMA")
      (footprint "eagle-import:SMADIODE")
      (libsource (lib "eagle-import") (part "DIODESMA"))
    )
    (comp (ref "D21")
      (value "DIODESMA")
      (footprint "eagle-import:SMADIODE")
      (libsource (lib "eagle-import") (part "DIODESMA"))
    )
    (comp (ref "D22")
      (value "DIODESMA")
      (footprint "eagle-import:SMADIODE")
      (libsource (lib "eagle-import") (part "DIODESMA"))
    )
    (comp (ref "D23")
      (value "DIODESMA")
      (footprint "eagle-import:SMADIODE")
      (libsource (lib "eagle-import") (part "DIODESMA"))
    )
    (comp (ref "D24")
      (value "DIODESMA")
      (footprint "eagle-import:SMADIODE")
      (libsource (lib "eagle-import") (part "DIODESMA"))
    )
    (comp (ref "D25")
      (value "DIODESMA")
      (footprint "eagle-import:SMADIODE")
      (libsource (lib "eagle-import") (part "DIODESMA"))
    )
    (comp (ref "D26")
      (value "DIODESMA")
      (footprint "eagle-import:SMADIODE")
      (libsource (lib "eagle-import") (part "DIODESMA"))
    )
    (comp (ref "D27")
      (value "DIODESMA")
      (footprint "eagle-import:SMADIODE")
      (libsource (lib "eagle-import") (part "DIODESMA"))
    )
    (comp (ref "D28")
      (value "DIODESMA")
      (footprint "eagle-import:SMADIODE")
      (libsource (lib "eagle-import") (part "DIODESMA"))
    )
    (comp (ref "D29")
      (value "DIODESMA")
      (footprint "eagle-import:SMADIODE")
      (libsource (lib "eagle-import") (part "DIODESMA"))
    )
    (comp (ref "D30")
      (value "DIODESMA")
      (footprint "eagle-import:SMADIODE")
      (libsource (lib "eagle-import") (part "DIODESMA"))
    )
    (comp (ref "D31")
      (value "DIODESMA")
      (footprint "eagle-import:SMADIODE")
      (libsource (lib "eagle-import") (part "DIODESMA"))
    )
    (comp (ref "D32")
      (value "DIODESMA")
      (footprint "eagle-import:SMADIODE")
      (libsource (lib "eagle-import") (part "DIODESMA"))
    )
    (comp (ref "D33")
      (value "DIODESMA")
      (footprint "eagle-import:SMADIODE")
      (libsource (lib "eagle-import") (part "DIODESMA"))
    )
    (comp (ref "D34")
      (value "DIODESMA")
      (footprint "eagle-import:SMADIODE")
      (libsource (lib "eagle-import") (part "DIODESMA"))
    )
    (comp (ref "D35")
      (value "DIODESMA")
      (footprint "eagle-import:SMADIODE")
      (libsource (lib "eagle-import") (part "DIODESMA"))
    )
    (comp (ref "D36")
      (value "DIODESMA")
      (footprint "eagle-import:SMADIODE")
      (libsource (lib "eagle-import") (part "DIODESMA"))
    )
    (comp (ref "D37")
      (value "DIODESMA")
      (footprint "eagle-import:SMADIODE")
      (libsource (lib "eagle-import") (part "DIODESMA"))
    )
    (comp (ref "D38")
      (value "DIODESMA")
      (footprint "eagle-import:SMADIODE")
      (libsource (lib "eagle-import") (part "DIODESMA"))
    )
    (comp (ref "D39")
      (value "DIODESMA")
      (footprint "eagle-import:SMADIODE")
      (libsource (lib "eagle-import") (part "DIODESMA"))
    )
    (comp (ref "D40")
      (value "DIODESMA")
      (footprint "eagle-import:SMADIODE")
      (libsource (lib "eagle-import") (part "DIODESMA"))
    )
    (comp (ref "D41")
      (value "DIODESMA")
      (footprint "eagle-import:SMADIODE")
      (libsource (lib "eagle-import") (part "DIODESMA"))
    )
    (comp (ref "D42")
      (value "DIODESMA")
      (footprint "eagle-import:SMADIODE")
      (libsource (lib "eagle-import") (part "DIODESMA"))
    )
    (comp (ref "D43")
      (value "DIODESMA")
      (footprint "eagle-import:SMADIODE")
      (libsource (lib "eagle-import") (part "DIODESMA"))
    )
    (comp (ref "D44")
      (value "DIODESMA")
      (footprint "eagle-import:SMADIODE")
      (libsource (lib "eagle-import") (part "DIODESMA"))
    )
    (comp (ref "D45")
      (value "DIODESMA")
      (footprint "eagle-import:SMADIODE")
      (libsource (lib "eagle-import") (part "DIODESMA"))
    )
    (comp (ref "D46")
      (value "DIODESMA")
      (footprint "eagle-import:SMADIODE")
      (libsource (lib "eagle-import") (part "DIODESMA"))
    )
    (comp (ref "D47")
      (value "DIODESMA")
      (footprint "eagle-import:SMADIODE")
      (libsource (lib "eagle-import") (part "DIODESMA"))
    )
    (comp (ref "D48")
      (value "DIODESMA")
      (footprint "eagle-import:SMADIODE")
      (libsource (lib "eagle-import") (part "DIODESMA"))
    )
    (comp (ref "D49")
      (value "DIODESMA")
      (footprint "eagle-import:SMADIODE")
      (libsource (lib "eagle-import") (part "DIODESMA"))
    )
    (comp (ref "D50")
      (value "DIODESMA")
      (footprint "eagle-import:SMADIODE")
      (libsource (lib "eagle-import") (part "DIODESMA"))
    )
    (comp (ref "D51")
      (value "DIODESMA")
      (footprint "eagle-import:SMADIODE")
      (libsource (lib "eagle-import") (part "DIODESMA"))
    )
    (comp (ref "D52")
      (value "DIODESMA")
      (footprint "eagle-import:SMADIODE")
      (libsource (lib "eagle-import") (part "DIODESMA"))
    )
    (comp (ref "D53")
      (value "DIODESMA")
      (footprint "eagle-import:SMADIODE")
      (libsource (lib "eagle-import") (part "DIODESMA"))
    )
    (comp (ref "D54")
      (value "DIODESMA")
      (footprint "eagle-import:SMADIODE")
      (libsource (lib "eagle-import") (part "DIODESMA"))
    )
    (comp (ref "D55")
      (value "DIODESMA")
      (footprint "eagle-import:SMADIODE")
      (libsource (lib "eagle-import") (part "DIODESMA"))
    )
    (comp (ref "D56")
      (value "DIODESMA")
      (footprint "eagle-import:SMADIODE")
      (libsource (lib "eagle-import") (part "DIODESMA"))
    )
    (comp (ref "D57")
      (value "DIODESMA")
      (footprint "eagle-import:SMADIODE")
      (libsource (lib "eagle-import") (part "DIODESMA"))
    )
    (comp (ref "D58")
      (value "DIODESMA")
      (footprint "eagle-import:SMADIODE")
      (libsource (lib "eagle-import") (part "DIODESMA"))
    )
    (comp (ref "D59")
      (value "DIODESMA")
      (footprint "eagle-import:SMADIODE")
      (libsource (lib "eagle-import") (part "DIODESMA"))
    )
    (comp (ref "D60")
      (value "DIODESMA")
      (footprint "eagle-import:SMADIODE")
      (libsource (lib "eagle-import") (part "DIODESMA"))
    )
    (comp (ref "N37")
      (value "A6")
      (footprint "eagle-import:EVQ-Q2")
      (libsource (lib "eagle-import") (part "SWITCH_TACT_SMT"))
    )
  )
  (nets
    (net (code "1") (name "1V8") (class "Default")
      (node (ref "C7") (pin "1") (pinfunction "1_1") (pintype "passive"))
      (node (ref "C9") (pin "1") (pinfunction "1_1") (pintype "passive"))
      (node (ref "J2") (pin "2") (pinfunction "2_2") (pintype "passive"))
      (node (ref "J7") (pin "2") (pinfunction "2_2") (pintype "passive"))
      (node (ref "L2") (pin "2") (pinfunction "2_2") (pintype "passive"))
    )
    (net (code "2") (name "3V3") (class "Default")
      (node (ref "C10") (pin "1") (pinfunction "1_1") (pintype "passive"))
      (node (ref "C17") (pin "1") (pinfunction "1_1") (pintype "passive"))
      (node (ref "C18") (pin "1") (pinfunction "1_1") (pintype "passive"))
      (node (ref "C19") (pin "1") (pinfunction "1_1") (pintype "passive"))
      (node (ref "C20") (pin "1") (pinfunction "1_1") (pintype "passive"))
      (node (ref "C6") (pin "1") (pinfunction "1_1") (pintype "passive"))
      (node (ref "C8") (pin "1") (pinfunction "1_1") (pintype "passive"))
      (node (ref "J1") (pin "2") (pinfunction "2_2") (pintype "passive"))
      (node (ref "J10") (pin "2") (pinfunction "2_2") (pintype "passive"))
      (node (ref "J11") (pin "1") (pinfunction "1_1") (pintype "passive"))
      (node (ref "J5") (pin "2") (pinfunction "2_2") (pintype "passive"))
      (node (ref "J6") (pin "2") (pinfunction "2_2") (pintype "passive"))
      (node (ref "L1") (pin "2") (pinfunction "2_2") (pintype "passive"))
      (node (ref "R6") (pin "2") (pinfunction "2_2") (pintype "passive"))
      (node (ref "U3") (pin "1") (pinfunction "VIN_1") (pintype "bidirectional"))
      (node (ref "U3") (pin "3") (pinfunction "EN_3") (pintype "bidirectional"))
    )
    (net (code "3") (name "5V") (class "Default")
      (node (ref "C1") (pin "1") (pinfunction "1_1") (pintype "passive"))
      (node (ref "C16") (pin "1") (pinfunction "1_1") (pintype "passive"))
      (node (ref "C3") (pin "1") (pinfunction "1_1") (pintype "passive"))
      (node (ref "C4") (pin "1") (pinfunction "1_1") (pintype "passive"))
      (node (ref "F1") (pin "P$2") (pinfunction "2_P$2") (pintype "passive"))
      (node (ref "J9") (pin "2") (pinfunction "2_2") (pintype "passive"))
      (node (ref "JP2") (pin "1") (pinfunction "1_1") (pintype "passive"))
      (node (ref "R7") (pin "2") (pinfunction "2_2") (pintype "passive"))
      (node (ref "U1") (pin "1") (pinfunction "IN_1") (pintype "bidirectional"))
      (node (ref "U1") (pin "3") (pinfunction "EN_3") (pintype "bidirectional"))
      (node (ref "U2") (pin "1") (pinfunction "VIN2_1") (pintype "bidirectional"))
      (node (ref "U2") (pin "6") (pinfunction "EN1_6") (pintype "bidirectional"))
      (node (ref "U2") (pin "7") (pinfunction "VIN1_7") (pintype "bidirectional"))
    )
    (net (code "4") (name "A") (class "Default")
      (node (ref "$$PCB100") (pin "66") (pinfunction "66/GPIO39_66") (pintype "bidirectional"))
      (node (ref "B17") (pin "1") (pinfunction "A_1") (pintype "bidirectional"))
    )
    (net (code "5") (name "B") (class "Default")
      (node (ref "$$PCB100") (pin "70") (pinfunction "70/GPIO40_70") (pintype "bidirectional"))
      (node (ref "B17") (pin "2") (pinfunction "B_2") (pintype "bidirectional"))
    )
    (net (code "6") (name "C") (class "Default")
      (node (ref "$$PCB100") (pin "72") (pinfunction "72/GPIO41_72") (pintype "bidirectional"))
      (node (ref "B17") (pin "3") (pinfunction "C_3") (pintype "bidirectional"))
    )
    (net (code "7") (name "CENTER") (class "Default")
      (node (ref "$$PCB100") (pin "76") (pinfunction "76/GPIO42_76") (pintype "bidirectional"))
      (node (ref "B17") (pin "6") (pinfunction "CENTER_6") (pintype "bidirectional"))
    )
    (net (code "8") (name "CM_1V8") (class "Default")
      (node (ref "$$PCB100") (pin "183") (pinfunction "183/1V8_183") (pintype "bidirectional"))
      (node (ref "$$PCB100") (pin "184") (pinfunction "184/1V8_184") (pintype "bidirectional"))
      (node (ref "$$PCB100") (pin "185") (pinfunction "185/1V8_185") (pintype "bidirectional"))
      (node (ref "$$PCB100") (pin "186") (pinfunction "186/1V8_186") (pintype "bidirectional"))
      (node (ref "C15") (pin "1") (pinfunction "1_1") (pintype "passive"))
      (node (ref "J7") (pin "1") (pinfunction "1_1") (pintype "passive"))
      (node (ref "JP2") (pin "5") (pinfunction "5_5") (pintype "passive"))
    )
    (net (code "9") (name "CM_3V3") (class "Default")
      (node (ref "$$PCB100") (pin "191") (pinfunction "191/3V3_191") (pintype "bidirectional"))
      (node (ref "$$PCB100") (pin "192") (pinfunction "192/3V3_192") (pintype "bidirectional"))
      (node (ref "$$PCB100") (pin "193") (pinfunction "193/3V3_193") (pintype "bidirectional"))
      (node (ref "$$PCB100") (pin "194") (pinfunction "194/3V3_194") (pintype "bidirectional"))
      (node (ref "C14") (pin "1") (pinfunction "1_1") (pintype "passive"))
      (node (ref "J6") (pin "1") (pinfunction "1_1") (pintype "passive"))
      (node (ref "JP2") (pin "3") (pinfunction "3_3") (pintype "passive"))
    )
    (net (code "10") (name "CM_VBAT") (class "Default")
      (node (ref "$$PCB100") (pin "197") (pinfunction "197/VBAT_197") (pintype "bidirectional"))
      (node (ref "$$PCB100") (pin "198") (pinfunction "198/VBAT_198") (pintype "bidirectional"))
      (node (ref "$$PCB100") (pin "199") (pinfunction "199/VBAT_199") (pintype "bidirectional"))
      (node (ref "$$PCB100") (pin "200") (pinfunction "200/VBAT_200") (pintype "bidirectional"))
      (node (ref "C13") (pin "1") (pinfunction "1_1") (pintype "passive"))
      (node (ref "J5") (pin "1") (pinfunction "1_1") (pintype "passive"))
      (node (ref "JP2") (pin "2") (pinfunction "2_2") (pintype "passive"))
    )
    (net (code "11") (name "CM_VDAC") (class "Default")
      (node (ref "$$PCB100") (pin "189") (pinfunction "189/VDAC_189") (pintype "bidirectional"))
      (node (ref "$$PCB100") (pin "190") (pinfunction "190/VDAC_190") (pintype "bidirectional"))
      (node (ref "J8") (pin "1") (pinfunction "1_1") (pintype "passive"))
      (node (ref "JP2") (pin "4") (pinfunction "4_4") (pintype "passive"))
    )
    (net (code "12") (name "COL_0") (class "Default")
      (node (ref "$$PCB100") (pin "69") (pinfunction "69/GPIO20_69") (pintype "bidirectional"))
      (node (ref "B1") (pin "B") (pinfunction "S_B") (pintype "passive"))
      (node (ref "B13") (pin "B") (pinfunction "S_B") (pintype "passive"))
      (node (ref "B19") (pin "B") (pinfunction "S_B") (pintype "passive"))
      (node (ref "B25") (pin "B") (pinfunction "S_B") (pintype "passive"))
      (node (ref "B31") (pin "B") (pinfunction "S_B") (pintype "passive"))
      (node (ref "B43") (pin "B") (pinfunction "S_B") (pintype "passive"))
      (node (ref "B49") (pin "B") (pinfunction "S_B") (pintype "passive"))
      (node (ref "B55") (pin "B") (pinfunction "S_B") (pintype "passive"))
      (node (ref "B7") (pin "B") (pinfunction "S_B") (pintype "passive"))
      (node (ref "N37") (pin "B") (pinfunction "S_B") (pintype "passive"))
    )
    (net (code "13") (name "COL_1") (class "Default")
      (node (ref "$$PCB100") (pin "71") (pinfunction "71/GPIO21_71") (pintype "bidirectional"))
      (node (ref "B14") (pin "B") (pinfunction "S_B") (pintype "passive"))
      (node (ref "B2") (pin "B") (pinfunction "S_B") (pintype "passive"))
      (node (ref "B20") (pin "B") (pinfunction "S_B") (pintype "passive"))
      (node (ref "B26") (pin "B") (pinfunction "S_B") (pintype "passive"))
      (node (ref "B32") (pin "B") (pinfunction "S_B") (pintype "passive"))
      (node (ref "B38") (pin "B") (pinfunction "S_B") (pintype "passive"))
      (node (ref "B44") (pin "B") (pinfunction "S_B") (pintype "passive"))
      (node (ref "B50") (pin "B") (pinfunction "S_B") (pintype "passive"))
      (node (ref "B56") (pin "B") (pinfunction "S_B") (pintype "passive"))
      (node (ref "B8") (pin "B") (pinfunction "S_B") (pintype "passive"))
    )
    (net (code "14") (name "COL_2") (class "Default")
      (node (ref "$$PCB100") (pin "75") (pinfunction "75/GPIO22_75") (pintype "bidirectional"))
      (node (ref "B15") (pin "B") (pinfunction "S_B") (pintype "passive"))
      (node (ref "B21") (pin "B") (pinfunction "S_B") (pintype "passive"))
      (node (ref "B27") (pin "B") (pinfunction "S_B") (pintype "passive"))
      (node (ref "B3") (pin "B") (pinfunction "S_B") (pintype "passive"))
      (node (ref "B33") (pin "B") (pinfunction "S_B") (pintype "passive"))
      (node (ref "B39") (pin "B") (pinfunction "S_B") (pintype "passive"))
      (node (ref "B45") (pin "B") (pinfunction "S_B") (pintype "passive"))
      (node (ref "B51") (pin "B") (pinfunction "S_B") (pintype "passive"))
      (node (ref "B57") (pin "B") (pinfunction "S_B") (pintype "passive"))
      (node (ref "B9") (pin "B") (pinfunction "S_B") (pintype "passive"))
    )
    (net (code "15") (name "COL_3") (class "Default")
      (node (ref "$$PCB100") (pin "77") (pinfunction "77/GPIO23_77") (pintype "bidirectional"))
      (node (ref "B10") (pin "B") (pinfunction "S_B") (pintype "passive"))
      (node (ref "B16") (pin "B") (pinfunction "S_B") (pintype "passive"))
      (node (ref "B22") (pin "B") (pinfunction "S_B") (pintype "passive"))
      (node (ref "B28") (pin "B") (pinfunction "S_B") (pintype "passive"))
      (node (ref "B34") (pin "B") (pinfunction "S_B") (pintype "passive"))
      (node (ref "B4") (pin "B") (pinfunction "S_B") (pintype "passive"))
      (node (ref "B40") (pin "B") (pinfunction "S_B") (pintype "passive"))
      (node (ref "B46") (pin "B") (pinfunction "S_B") (pintype "passive"))
      (node (ref "B52") (pin "B") (pinfunction "S_B") (pintype "passive"))
      (node (ref "B58") (pin "B") (pinfunction "S_B") (pintype "passive"))
    )
    (net (code "16") (name "COL_4") (class "Default")
      (node (ref "$$PCB100") (pin "87") (pinfunction "87/GPIO26_87") (pintype "bidirectional"))
      (node (ref "B11") (pin "B") (pinfunction "S_B") (pintype "passive"))
      (node (ref "B23") (pin "B") (pinfunction "S_B") (pintype "passive"))
      (node (ref "B29") (pin "B") (pinfunction "S_B") (pintype "passive"))
      (node (ref "B35") (pin "B") (pinfunction "S_B") (pintype "passive"))
      (node (ref "B41") (pin "B") (pinfunction "S_B") (pintype "passive"))
      (node (ref "B47") (pin "B") (pinfunction "S_B") (pintype "passive"))
      (node (ref "B5") (pin "B") (pinfunction "S_B") (pintype "passive"))
      (node (ref "B53") (pin "B") (pinfunction "S_B") (pintype "passive"))
      (node (ref "B59") (pin "B") (pinfunction "S_B") (pintype "passive"))
    )
    (net (code "17") (name "COL_5") (class "Default")
      (node (ref "$$PCB100") (pin "89") (pinfunction "89/GPIO27_89") (pintype "bidirectional"))
      (node (ref "B12") (pin "B") (pinfunction "S_B") (pintype "passive"))
      (node (ref "B18") (pin "B") (pinfunction "S_B") (pintype "passive"))
      (node (ref "B24") (pin "B") (pinfunction "S_B") (pintype "passive"))
      (node (ref "B30") (pin "B") (pinfunction "S_B") (pintype "passive"))
      (node (ref "B36") (pin "B") (pinfunction "S_B") (pintype "passive"))
      (node (ref "B42") (pin "B") (pinfunction "S_B") (pintype "passive"))
      (node (ref "B48") (pin "B") (pinfunction "S_B") (pintype "passive"))
      (node (ref "B54") (pin "B") (pinfunction "S_B") (pintype "passive"))
      (node (ref "B6") (pin "B") (pinfunction "S_B") (pintype "passive"))
      (node (ref "B60") (pin "B") (pinfunction "S_B") (pintype "passive"))
    )
    (net (code "18") (name "COMMON") (class "Default")
      (node (ref "$$PCB100") (pin "134") (pinfunction "134/GND_134") (pintype "bidirectional"))
      (node (ref "B17") (pin "4") (pinfunction "COMMON_4") (pintype "bidirectional"))
    )
    (net (code "19") (name "D") (class "Default")
      (node (ref "$$PCB100") (pin "78") (pinfunction "78/GPIO43_78") (pintype "bidirectional"))
      (node (ref "B17") (pin "5") (pinfunction "D_5") (pintype "bidirectional"))
    )
    (net (code "20") (name "DAC_2V5") (class "Default")
      (node (ref "C11") (pin "1") (pinfunction "1_1") (pintype "passive"))
      (node (ref "J8") (pin "2") (pinfunction "2_2") (pintype "passive"))
      (node (ref "U3") (pin "5") (pinfunction "VOUT_5") (pintype "bidirectional"))
    )
    (net (code "21") (name "DCIN") (class "Default")
      (node (ref "F1") (pin "P$1") (pinfunction "1_P$1") (pintype "passive"))
      (node (ref "JP1") (pin "1") (pinfunction "1_1") (pintype "passive"))
    )
    (net (code "22") (name "EMMC_DISABLE_N") (class "Default")
      (node (ref "$$PCB100") (pin "2") (pinfunction "2/EMMC_DISABLE_N_2") (pintype "bidirectional"))
    )
    (net (code "23") (name "GND") (class "Default")
      (node (ref "C1") (pin "2") (pinfunction "2_2") (pintype "passive"))
      (node (ref "C10") (pin "2") (pinfunction "2_2") (pintype "passive"))
      (node (ref "C11") (pin "2") (pinfunction "2_2") (pintype "passive"))
      (node (ref "C12") (pin "2") (pinfunction "2_2") (pintype "passive"))
      (node (ref "C13") (pin "2") (pinfunction "2_2") (pintype "passive"))
      (node (ref "C14") (pin "2") (pinfunction "2_2") (pintype "passive"))
      (node (ref "C15") (pin "2") (pinfunction "2_2") (pintype "passive"))
      (node (ref "C16") (pin "2") (pinfunction "2_2") (pintype "passive"))
      (node (ref "C17") (pin "2") (pinfunction "2_2") (pintype "passive"))
      (node (ref "C18") (pin "2") (pinfunction "2_2") (pintype "passive"))
      (node (ref "C19") (pin "2") (pinfunction "2_2") (pintype "passive"))
      (node (ref "C2") (pin "2") (pinfunction "2_2") (pintype "passive"))
      (node (ref "C20") (pin "2") (pinfunction "2_2") (pintype "passive"))
      (node (ref "C21") (pin "2") (pinfunction "2_2") (pintype "passive"))
      (node (ref "C22") (pin "2") (pinfunction "2_2") (pintype "passive"))
      (node (ref "C23") (pin "2") (pinfunction "2_2") (pintype "passive"))
      (node (ref "C24") (pin "2") (pinfunction "2_2") (pintype "passive"))
      (node (ref "C3") (pin "2") (pinfunction "2_2") (pintype "passive"))
      (node (ref "C4") (pin "2") (pinfunction "2_2") (pintype "passive"))
      (node (ref "C8") (pin "2") (pinfunction "2_2") (pintype "passive"))
      (node (ref "C9") (pin "2") (pinfunction "2_2") (pintype "passive"))
      (node (ref "J12") (pin "4") (pinfunction "4_4") (pintype "passive"))
      (node (ref "J3") (pin "1") (pinfunction "1_1") (pintype "passive"))
      (node (ref "J4") (pin "1") (pinfunction "1_1") (pintype "passive"))
      (node (ref "JP1") (pin "2") (pinfunction "2_2") (pintype "passive"))
      (node (ref "LED1") (pin "C") (pinfunction "C_C") (pintype "passive"))
      (node (ref "Q1") (pin "2") (pinfunction "E_2") (pintype "passive"))
      (node (ref "R1") (pin "1") (pinfunction "1_1") (pintype "passive"))
      (node (ref "R2") (pin "1") (pinfunction "1_1") (pintype "passive"))
      (node (ref "R3") (pin "1") (pinfunction "1_1") (pintype "passive"))
      (node (ref "R4") (pin "1") (pinfunction "1_1") (pintype "passive"))
      (node (ref "R5") (pin "1") (pinfunction "1_1") (pintype "passive"))
      (node (ref "R9") (pin "2") (pinfunction "2_2") (pintype "passive"))
      (node (ref "TFT1") (pin "43") (pinfunction "GND_43") (pintype "bidirectional"))
      (node (ref "TFT1") (pin "48") (pinfunction "GND_48") (pintype "bidirectional"))
      (node (ref "TFT1") (pin "49") (pinfunction "GND_49") (pintype "bidirectional"))
      (node (ref "TFT1") (pin "50") (pinfunction "GND_50") (pintype "bidirectional"))
      (node (ref "TFT1") (pin "6") (pinfunction "IM0_6") (pintype "bidirectional"))
      (node (ref "U1") (pin "2") (pinfunction "GND_2") (pintype "bidirectional"))
      (node (ref "U2") (pin "13") (pinfunction "PAD_13") (pintype "bidirectional"))
      (node (ref "U2") (pin "3") (pinfunction "GND_3") (pintype "bidirectional"))
      (node (ref "U2") (pin "9") (pinfunction "GND_9") (pintype "bidirectional"))
      (node (ref "U3") (pin "2") (pinfunction "GND_2") (pintype "bidirectional"))
      (node (ref "U4") (pin "1") (pinfunction "GND_1") (pintype "power_in"))
      (node (ref "UTSC") (pin "10") (pinfunction "GND_10") (pintype "bidirectional"))
    )
    (net (code "24") (name "GPIO0-27_VREF") (class "Default")
      (node (ref "$$PCB100") (pin "40") (pinfunction "40/GPIO0-27_VREF_40") (pintype "bidirectional"))
      (node (ref "C21") (pin "1") (pinfunction "1_1") (pintype "passive"))
      (node (ref "J10") (pin "1") (pinfunction "1_1") (pintype "passive"))
      (node (ref "JP2") (pin "6") (pinfunction "6_6") (pintype "passive"))
    )
    (net (code "25") (name "GPIO28-45_VREF") (class "Default")
      (node (ref "$$PCB100") (pin "42") (pinfunction "42/GPIO28-45_VREF_42") (pintype "bidirectional"))
      (node (ref "C22") (pin "1") (pinfunction "1_1") (pintype "passive"))
      (node (ref "J11") (pin "2") (pinfunction "2_2") (pintype "passive"))
      (node (ref "JP2") (pin "7") (pinfunction "7_7") (pintype "passive"))
    )
    (net (code "26") (name "GPIO46_1V8") (class "Default")
      (node (ref "$$PCB100") (pin "88") (pinfunction "88/GPIO46_1V8_88") (pintype "bidirectional"))
    )
    (net (code "27") (name "MISO") (class "Default")
      (node (ref "$$PCB100") (pin "29") (pinfunction "29/GPIO9_29") (pintype "bidirectional"))
      (node (ref "TFT1") (pin "33") (pinfunction "SDO_33") (pintype "bidirectional"))
      (node (ref "UTSC") (pin "3") (pinfunction "A0/DATA_OUT_3") (pintype "bidirectional"))
    )
    (net (code "28") (name "MOSI") (class "Default")
      (node (ref "$$PCB100") (pin "33") (pinfunction "33/GPIO10_33") (pintype "bidirectional"))
      (node (ref "R18") (pin "2") (pinfunction "2_2") (pintype "passive"))
      (node (ref "TFT1") (pin "34") (pinfunction "SDI_34") (pintype "bidirectional"))
      (node (ref "UTSC") (pin "7") (pinfunction "DATA_IN_7") (pintype "bidirectional"))
    )
    (net (code "29") (name "Net-($$PCB100-28{slash}GPIO28)") (class "Default")
      (node (ref "$$PCB100") (pin "28") (pinfunction "28/GPIO28_28") (pintype "bidirectional"))
      (node (ref "R1") (pin "2") (pinfunction "2_2") (pintype "passive"))
    )
    (net (code "30") (name "Net-($$PCB100-30{slash}GPIO29)") (class "Default")
      (node (ref "$$PCB100") (pin "30") (pinfunction "30/GPIO29_30") (pintype "bidirectional"))
      (node (ref "R2") (pin "2") (pinfunction "2_2") (pintype "passive"))
    )
    (net (code "31") (name "Net-($$PCB100-82{slash}GPIO44)") (class "Default")
      (node (ref "$$PCB100") (pin "82") (pinfunction "82/GPIO44_82") (pintype "bidirectional"))
      (node (ref "R3") (pin "2") (pinfunction "2_2") (pintype "passive"))
    )
    (net (code "32") (name "Net-($$PCB100-84{slash}GPIO45)") (class "Default")
      (node (ref "$$PCB100") (pin "84") (pinfunction "84/GPIO45_84") (pintype "bidirectional"))
      (node (ref "R4") (pin "2") (pinfunction "2_2") (pintype "passive"))
    )
    (net (code "33") (name "Net-($$PCB100-168{slash}USB_OTGID)") (class "Default")
      (node (ref "$$PCB100") (pin "168") (pinfunction "168/USB_OTGID_168") (pintype "bidirectional"))
      (node (ref "R5") (pin "2") (pinfunction "2_2") (pintype "passive"))
    )
    (net (code "34") (name "Net-(B1-P)") (class "Default")
      (node (ref "B1") (pin "A") (pinfunction "P_A") (pintype "passive"))
      (node (ref "D1") (pin "A") (pinfunction "A_A") (pintype "passive"))
    )
    (net (code "35") (name "Net-(B2-P)") (class "Default")
      (node (ref "B2") (pin "A") (pinfunction "P_A") (pintype "passive"))
      (node (ref "D2") (pin "A") (pinfunction "A_A") (pintype "passive"))
    )
    (net (code "36") (name "Net-(B3-P)") (class "Default")
      (node (ref "B3") (pin "A") (pinfunction "P_A") (pintype "passive"))
      (node (ref "D3") (pin "A") (pinfunction "A_A") (pintype "passive"))
    )
    (net (code "37") (name "Net-(B4-P)") (class "Default")
      (node (ref "B4") (pin "A") (pinfunction "P_A") (pintype "passive"))
      (node (ref "D4") (pin "A") (pinfunction "A_A") (pintype "passive"))
    )
    (net (code "38") (name "Net-(B5-P)") (class "Default")
      (node (ref "B5") (pin "A") (pinfunction "P_A") (pintype "passive"))
      (node (ref "D5") (pin "A") (pinfunction "A_A") (pintype "passive"))
    )
    (net (code "39") (name "Net-(B6-P)") (class "Default")
      (node (ref "B6") (pin "A") (pinfunction "P_A") (pintype "passive"))
      (node (ref "D6") (pin "A") (pinfunction "A_A") (pintype "passive"))
    )
    (net (code "40") (name "Net-(B7-P)") (class "Default")
      (node (ref "B7") (pin "A") (pinfunction "P_A") (pintype "passive"))
      (node (ref "D7") (pin "A") (pinfunction "A_A") (pintype "passive"))
    )
    (net (code "41") (name "Net-(B8-P)") (class "Default")
      (node (ref "B8") (pin "A") (pinfunction "P_A") (pintype "passive"))
      (node (ref "D8") (pin "A") (pinfunction "A_A") (pintype "passive"))
    )
    (net (code "42") (name "Net-(B9-P)") (class "Default")
      (node (ref "B9") (pin "A") (pinfunction "P_A") (pintype "passive"))
      (node (ref "D9") (pin "A") (pinfunction "A_A") (pintype "passive"))
    )
    (net (code "43") (name "Net-(B10-P)") (class "Default")
      (node (ref "B10") (pin "A") (pinfunction "P_A") (pintype "passive"))
      (node (ref "D10") (pin "A") (pinfunction "A_A") (pintype "passive"))
    )
    (net (code "44") (name "Net-(B11-P)") (class "Default")
      (node (ref "B11") (pin "A") (pinfunction "P_A") (pintype "passive"))
      (node (ref "D11") (pin "A") (pinfunction "A_A") (pintype "passive"))
    )
    (net (code "45") (name "Net-(B12-P)") (class "Default")
      (node (ref "B12") (pin "A") (pinfunction "P_A") (pintype "passive"))
      (node (ref "D12") (pin "A") (pinfunction "A_A") (pintype "passive"))
    )
    (net (code "46") (name "Net-(B13-P)") (class "Default")
      (node (ref "B13") (pin "A") (pinfunction "P_A") (pintype "passive"))
      (node (ref "D13") (pin "A") (pinfunction "A_A") (pintype "passive"))
    )
    (net (code "47") (name "Net-(B14-P)") (class "Default")
      (node (ref "B14") (pin "A") (pinfunction "P_A") (pintype "passive"))
      (node (ref "D14") (pin "A") (pinfunction "A_A") (pintype "passive"))
    )
    (net (code "48") (name "Net-(B15-P)") (class "Default")
      (node (ref "B15") (pin "A") (pinfunction "P_A") (pintype "passive"))
      (node (ref "D15") (pin "A") (pinfunction "A_A") (pintype "passive"))
    )
    (net (code "49") (name "Net-(B16-P)") (class "Default")
      (node (ref "B16") (pin "A") (pinfunction "P_A") (pintype "passive"))
      (node (ref "D16") (pin "A") (pinfunction "A_A") (pintype "passive"))
    )
    (net (code "50") (name "Net-(B18-P)") (class "Default")
      (node (ref "B18") (pin "A") (pinfunction "P_A") (pintype "passive"))
      (node (ref "D18") (pin "A") (pinfunction "A_A") (pintype "passive"))
    )
    (net (code "51") (name "Net-(B19-P)") (class "Default")
      (node (ref "B19") (pin "A") (pinfunction "P_A") (pintype "passive"))
      (node (ref "D19") (pin "A") (pinfunction "A_A") (pintype "passive"))
    )
    (net (code "52") (name "Net-(B20-P)") (class "Default")
      (node (ref "B20") (pin "A") (pinfunction "P_A") (pintype "passive"))
      (node (ref "D20") (pin "A") (pinfunction "A_A") (pintype "passive"))
    )
    (net (code "53") (name "Net-(B21-P)") (class "Default")
      (node (ref "B21") (pin "A") (pinfunction "P_A") (pintype "passive"))
      (node (ref "D21") (pin "A") (pinfunction "A_A") (pintype "passive"))
    )
    (net (code "54") (name "Net-(B22-P)") (class "Default")
      (node (ref "B22") (pin "A") (pinfunction "P_A") (pintype "passive"))
      (node (ref "D22") (pin "A") (pinfunction "A_A") (pintype "passive"))
    )
    (net (code "55") (name "Net-(B23-P)") (class "Default")
      (node (ref "B23") (pin "A") (pinfunction "P_A") (pintype "passive"))
      (node (ref "D23") (pin "A") (pinfunction "A_A") (pintype "passive"))
    )
    (net (code "56") (name "Net-(B24-P)") (class "Default")
      (node (ref "B24") (pin "A") (pinfunction "P_A") (pintype "passive"))
      (node (ref "D24") (pin "A") (pinfunction "A_A") (pintype "passive"))
    )
    (net (code "57") (name "Net-(B25-P)") (class "Default")
      (node (ref "B25") (pin "A") (pinfunction "P_A") (pintype "passive"))
      (node (ref "D25") (pin "A") (pinfunction "A_A") (pintype "passive"))
    )
    (net (code "58") (name "Net-(B26-P)") (class "Default")
      (node (ref "B26") (pin "A") (pinfunction "P_A") (pintype "passive"))
      (node (ref "D26") (pin "A") (pinfunction "A_A") (pintype "passive"))
    )
    (net (code "59") (name "Net-(B27-P)") (class "Default")
      (node (ref "B27") (pin "A") (pinfunction "P_A") (pintype "passive"))
      (node (ref "D27") (pin "A") (pinfunction "A_A") (pintype "passive"))
    )
    (net (code "60") (name "Net-(B28-P)") (class "Default")
      (node (ref "B28") (pin "A") (pinfunction "P_A") (pintype "passive"))
      (node (ref "D28") (pin "A") (pinfunction "A_A") (pintype "passive"))
    )
    (net (code "61") (name "Net-(B29-P)") (class "Default")
      (node (ref "B29") (pin "A") (pinfunction "P_A") (pintype "passive"))
      (node (ref "D29") (pin "A") (pinfunction "A_A") (pintype "passive"))
    )
    (net (code "62") (name "Net-(B30-P)") (class "Default")
      (node (ref "B30") (pin "A") (pinfunction "P_A") (pintype "passive"))
      (node (ref "D30") (pin "A") (pinfunction "A_A") (pintype "passive"))
    )
    (net (code "63") (name "Net-(B31-P)") (class "Default")
      (node (ref "B31") (pin "A") (pinfunction "P_A") (pintype "passive"))
      (node (ref "D31") (pin "A") (pinfunction "A_A") (pintype "passive"))
    )
    (net (code "64") (name "Net-(B32-P)") (class "Default")
      (node (ref "B32") (pin "A") (pinfunction "P_A") (pintype "passive"))
      (node (ref "D32") (pin "A") (pinfunction "A_A") (pintype "passive"))
    )
    (net (code "65") (name "Net-(B33-P)") (class "Default")
      (node (ref "B33") (pin "A") (pinfunction "P_A") (pintype "passive"))
      (node (ref "D33") (pin "A") (pinfunction "A_A") (pintype "passive"))
    )
    (net (code "66") (name "Net-(B34-P)") (class "Default")
      (node (ref "B34") (pin "A") (pinfunction "P_A") (pintype "passive"))
      (node (ref "D34") (pin "A") (pinfunction "A_A") (pintype "passive"))
    )
    (net (code "67") (name "Net-(B35-P)") (class "Default")
      (node (ref "B35") (pin "A") (pinfunction "P_A") (pintype "passive"))
      (node (ref "D35") (pin "A") (pinfunction "A_A") (pintype "passive"))
    )
    (net (code "68") (name "Net-(B36-P)") (class "Default")
      (node (ref "B36") (pin "A") (pinfunction "P_A") (pintype "passive"))
      (node (ref "D36") (pin "A") (pinfunction "A_A") (pintype "passive"))
    )
    (net (code "69") (name "Net-(B38-P)") (class "Default")
      (node (ref "B38") (pin "A") (pinfunction "P_A") (pintype "passive"))
      (node (ref "D38") (pin "A") (pinfunction "A_A") (pintype "passive"))
    )
    (net (code "70") (name "Net-(B39-P)") (class "Default")
      (node (ref "B39") (pin "A") (pinfunction "P_A") (pintype "passive"))
      (node (ref "D39") (pin "A") (pinfunction "A_A") (pintype "passive"))
    )
    (net (code "71") (name "Net-(B40-P)") (class "Default")
      (node (ref "B40") (pin "A") (pinfunction "P_A") (pintype "passive"))
      (node (ref "D40") (pin "A") (pinfunction "A_A") (pintype "passive"))
    )
    (net (code "72") (name "Net-(B41-P)") (class "Default")
      (node (ref "B41") (pin "A") (pinfunction "P_A") (pintype "passive"))
      (node (ref "D41") (pin "A") (pinfunction "A_A") (pintype "passive"))
    )
    (net (code "73") (name "Net-(B42-P)") (class "Default")
      (node (ref "B42") (pin "A") (pinfunction "P_A") (pintype "passive"))
      (node (ref "D42") (pin "A") (pinfunction "A_A") (pintype "passive"))
    )
    (net (code "74") (name "Net-(B43-P)") (class "Default")
      (node (ref "B43") (pin "A") (pinfunction "P_A") (pintype "passive"))
      (node (ref "D43") (pin "A") (pinfunction "A_A") (pintype "passive"))
    )
    (net (code "75") (name "Net-(B44-P)") (class "Default")
      (node (ref "B44") (pin "A") (pinfunction "P_A") (pintype "passive"))
      (node (ref "D44") (pin "A") (pinfunction "A_A") (pintype "passive"))
    )
    (net (code "76") (name "Net-(B45-P)") (class "Default")
      (node (ref "B45") (pin "A") (pinfunction "P_A") (pintype "passive"))
      (node (ref "D45") (pin "A") (pinfunction "A_A") (pintype "passive"))
    )
    (net (code "77") (name "Net-(B46-P)") (class "Default")
      (node (ref "B46") (pin "A") (pinfunction "P_A") (pintype "passive"))
      (node (ref "D46") (pin "A") (pinfunction "A_A") (pintype "passive"))
    )
    (net (code "78") (name "Net-(B47-P)") (class "Default")
      (node (ref "B47") (pin "A") (pinfunction "P_A") (pintype "passive"))
      (node (ref "D47") (pin "A") (pinfunction "A_A") (pintype "passive"))
    )
    (net (code "79") (name "Net-(B48-P)") (class "Default")
      (node (ref "B48") (pin "A") (pinfunction "P_A") (pintype "passive"))
      (node (ref "D48") (pin "A") (pinfunction "A_A") (pintype "passive"))
    )
    (net (code "80") (name "Net-(B49-P)") (class "Default")
      (node (ref "B49") (pin "A") (pinfunction "P_A") (pintype "passive"))
      (node (ref "D49") (pin "A") (pinfunction "A_A") (pintype "passive"))
    )
    (net (code "81") (name "Net-(B50-P)") (class "Default")
      (node (ref "B50") (pin "A") (pinfunction "P_A") (pintype "passive"))
      (node (ref "D50") (pin "A") (pinfunction "A_A") (pintype "passive"))
    )
    (net (code "82") (name "Net-(B51-P)") (class "Default")
      (node (ref "B51") (pin "A") (pinfunction "P_A") (pintype "passive"))
      (node (ref "D51") (pin "A") (pinfunction "A_A") (pintype "passive"))
    )
    (net (code "83") (name "Net-(B52-P)") (class "Default")
      (node (ref "B52") (pin "A") (pinfunction "P_A") (pintype "passive"))
      (node (ref "D52") (pin "A") (pinfunction "A_A") (pintype "passive"))
    )
    (net (code "84") (name "Net-(B53-P)") (class "Default")
      (node (ref "B53") (pin "A") (pinfunction "P_A") (pintype "passive"))
      (node (ref "D53") (pin "A") (pinfunction "A_A") (pintype "passive"))
    )
    (net (code "85") (name "Net-(B54-P)") (class "Default")
      (node (ref "B54") (pin "A") (pinfunction "P_A") (pintype "passive"))
      (node (ref "D54") (pin "A") (pinfunction "A_A") (pintype "passive"))
    )
    (net (code "86") (name "Net-(B55-P)") (class "Default")
      (node (ref "B55") (pin "A") (pinfunction "P_A") (pintype "passive"))
      (node (ref "D55") (pin "A") (pinfunction "A_A") (pintype "passive"))
    )
    (net (code "87") (name "Net-(B56-P)") (class "Default")
      (node (ref "B56") (pin "A") (pinfunction "P_A") (pintype "passive"))
      (node (ref "D56") (pin "A") (pinfunction "A_A") (pintype "passive"))
    )
    (net (code "88") (name "Net-(B57-P)") (class "Default")
      (node (ref "B57") (pin "A") (pinfunction "P_A") (pintype "passive"))
      (node (ref "D57") (pin "A") (pinfunction "A_A") (pintype "passive"))
    )
    (net (code "89") (name "Net-(B58-P)") (class "Default")
      (node (ref "B58") (pin "A") (pinfunction "P_A") (pintype "passive"))
      (node (ref "D58") (pin "A") (pinfunction "A_A") (pintype "passive"))
    )
    (net (code "90") (name "Net-(B59-P)") (class "Default")
      (node (ref "B59") (pin "A") (pinfunction "P_A") (pintype "passive"))
      (node (ref "D59") (pin "A") (pinfunction "A_A") (pintype "passive"))
    )
    (net (code "91") (name "Net-(B60-P)") (class "Default")
      (node (ref "B60") (pin "A") (pinfunction "P_A") (pintype "passive"))
      (node (ref "D60") (pin "A") (pinfunction "A_A") (pintype "passive"))
    )
    (net (code "92") (name "Net-(LED1-PadA)") (class "Default")
      (node (ref "LED1") (pin "A") (pinfunction "A_A") (pintype "passive"))
      (node (ref "R6") (pin "1") (pinfunction "1_1") (pintype "passive"))
    )
    (net (code "93") (name "Net-(N37-P)") (class "Default")
      (node (ref "D37") (pin "A") (pinfunction "A_A") (pintype "passive"))
      (node (ref "N37") (pin "A") (pinfunction "P_A") (pintype "passive"))
    )
    (net (code "94") (name "Net-(Q1-B)") (class "Default")
      (node (ref "Q1") (pin "1") (pinfunction "B_1") (pintype "passive"))
      (node (ref "R12") (pin "2") (pinfunction "2_2") (pintype "passive"))
    )
    (net (code "95") (name "Net-(Q1-C)") (class "Default")
      (node (ref "Q1") (pin "3") (pinfunction "C_3") (pintype "passive"))
      (node (ref "TFT1") (pin "1") (pinfunction "LEDK_1") (pintype "bidirectional"))
    )
    (net (code "96") (name "Net-(R13-Pad1)") (class "Default")
      (node (ref "R13") (pin "1") (pinfunction "1_1") (pintype "passive"))
      (node (ref "TFT1") (pin "2") (pinfunction "LEDA_2") (pintype "bidirectional"))
    )
    (net (code "97") (name "Net-(R14-Pad1)") (class "Default")
      (node (ref "R14") (pin "1") (pinfunction "1_1") (pintype "passive"))
      (node (ref "TFT1") (pin "3") (pinfunction "LEDA_3") (pintype "bidirectional"))
    )
    (net (code "98") (name "Net-(R15-Pad1)") (class "Default")
      (node (ref "R15") (pin "1") (pinfunction "1_1") (pintype "passive"))
      (node (ref "TFT1") (pin "4") (pinfunction "LEDA_4") (pintype "bidirectional"))
    )
    (net (code "99") (name "Net-(R16-Pad1)") (class "Default")
      (node (ref "R16") (pin "1") (pinfunction "1_1") (pintype "passive"))
      (node (ref "TFT1") (pin "5") (pinfunction "LEDA_5") (pintype "bidirectional"))
    )
    (net (code "100") (name "Net-(TFT1-DB0)") (class "Default")
      (node (ref "TFT1") (pin "15") (pinfunction "DB17_15") (pintype "bidirectional"))
      (node (ref "TFT1") (pin "16") (pinfunction "DB16_16") (pintype "bidirectional"))
      (node (ref "TFT1") (pin "17") (pinfunction "DB15_17") (pintype "bidirectional"))
      (node (ref "TFT1") (pin "18") (pinfunction "DB14_18") (pintype "bidirectional"))
      (node (ref "TFT1") (pin "19") (pinfunction "DB13_19") (pintype "bidirectional"))
      (node (ref "TFT1") (pin "20") (pinfunction "DB12_20") (pintype "bidirectional"))
      (node (ref "TFT1") (pin "21") (pinfunction "DB11_21") (pintype "bidirectional"))
      (node (ref "TFT1") (pin "22") (pinfunction "DB10_22") (pintype "bidirectional"))
      (node (ref "TFT1") (pin "23") (pinfunction "DB9_23") (pintype "bidirectional"))
      (node (ref "TFT1") (pin "24") (pinfunction "DB8_24") (pintype "bidirectional"))
      (node (ref "TFT1") (pin "25") (pinfunction "DB7_25") (pintype "bidirectional"))
      (node (ref "TFT1") (pin "26") (pinfunction "DB6_26") (pintype "bidirectional"))
      (node (ref "TFT1") (pin "27") (pinfunction "DB5_27") (pintype "bidirectional"))
      (node (ref "TFT1") (pin "28") (pinfunction "DB4_28") (pintype "bidirectional"))
      (node (ref "TFT1") (pin "29") (pinfunction "DB3_29") (pintype "bidirectional"))
      (node (ref "TFT1") (pin "30") (pinfunction "DB2_30") (pintype "bidirectional"))
      (node (ref "TFT1") (pin "31") (pinfunction "DB1_31") (pintype "bidirectional"))
      (node (ref "TFT1") (pin "32") (pinfunction "DB0_32") (pintype "bidirectional"))
    )
    (net (code "101") (name "Net-(TFT1-{slash}RESET)") (class "Default")
      (node (ref "R10") (pin "1") (pinfunction "1_1") (pintype "passive"))
      (node (ref "TFT1") (pin "10") (pinfunction "/RESET_10") (pintype "bidirectional"))
      (node (ref "U4") (pin "2") (pinfunction "/RESET_2") (pintype "output"))
    )
    (net (code "102") (name "Net-(U2-EN2)") (class "Default")
      (node (ref "C2") (pin "1") (pinfunction "1_1") (pintype "passive"))
      (node (ref "R7") (pin "1") (pinfunction "1_1") (pintype "passive"))
      (node (ref "U2") (pin "12") (pinfunction "EN2_12") (pintype "bidirectional"))
    )
    (net (code "103") (name "Net-(U2-FB1)") (class "Default")
      (node (ref "C6") (pin "2") (pinfunction "2_2") (pintype "passive"))
      (node (ref "J1") (pin "1") (pinfunction "1_1") (pintype "passive"))
      (node (ref "J4") (pin "2") (pinfunction "2_2") (pintype "passive"))
      (node (ref "U2") (pin "2") (pinfunction "FB1_2") (pintype "bidirectional"))
    )
    (net (code "104") (name "Net-(U2-FB2)") (class "Default")
      (node (ref "C7") (pin "2") (pinfunction "2_2") (pintype "passive"))
      (node (ref "J2") (pin "1") (pinfunction "1_1") (pintype "passive"))
      (node (ref "J3") (pin "2") (pinfunction "2_2") (pintype "passive"))
      (node (ref "U2") (pin "10") (pinfunction "FB2_10") (pintype "bidirectional"))
    )
    (net (code "105") (name "Net-(U2-LX1)") (class "Default")
      (node (ref "L1") (pin "1") (pinfunction "1_1") (pintype "passive"))
      (node (ref "U2") (pin "8") (pinfunction "LX1_8") (pintype "bidirectional"))
    )
    (net (code "106") (name "Net-(U2-LX2)") (class "Default")
      (node (ref "L2") (pin "1") (pinfunction "1_1") (pintype "passive"))
      (node (ref "U2") (pin "4") (pinfunction "LX2_4") (pintype "bidirectional"))
    )
    (net (code "107") (name "Net-(U3-BYP)") (class "Default")
      (node (ref "C12") (pin "1") (pinfunction "1_1") (pintype "passive"))
      (node (ref "U3") (pin "4") (pinfunction "BYP_4") (pintype "bidirectional"))
    )
    (net (code "108") (name "Net-(UTSC-IN2{slash}GPIO-2)") (class "Default")
      (node (ref "R11") (pin "2") (pinfunction "2_2") (pintype "passive"))
      (node (ref "R12") (pin "1") (pinfunction "1_1") (pintype "passive"))
      (node (ref "UTSC") (pin "11") (pinfunction "IN2/GPIO-2_11") (pintype "bidirectional"))
    )
    (net (code "109") (name "ROW_0") (class "Default")
      (node (ref "$$PCB100") (pin "3") (pinfunction "3/GPIO0_3") (pintype "bidirectional"))
      (node (ref "D1") (pin "C") (pinfunction "C_C") (pintype "passive"))
      (node (ref "D2") (pin "C") (pinfunction "C_C") (pintype "passive"))
      (node (ref "D3") (pin "C") (pinfunction "C_C") (pintype "passive"))
      (node (ref "D4") (pin "C") (pinfunction "C_C") (pintype "passive"))
      (node (ref "D5") (pin "C") (pinfunction "C_C") (pintype "passive"))
      (node (ref "D6") (pin "C") (pinfunction "C_C") (pintype "passive"))
    )
    (net (code "110") (name "ROW_1") (class "Default")
      (node (ref "$$PCB100") (pin "60") (pinfunction "60/GPIO37_60") (pintype "bidirectional"))
      (node (ref "D10") (pin "C") (pinfunction "C_C") (pintype "passive"))
      (node (ref "D11") (pin "C") (pinfunction "C_C") (pintype "passive"))
      (node (ref "D12") (pin "C") (pinfunction "C_C") (pintype "passive"))
      (node (ref "D7") (pin "C") (pinfunction "C_C") (pintype "passive"))
      (node (ref "D8") (pin "C") (pinfunction "C_C") (pintype "passive"))
      (node (ref "D9") (pin "C") (pinfunction "C_C") (pintype "passive"))
    )
    (net (code "111") (name "ROW_2") (class "Default")
      (node (ref "$$PCB100") (pin "58") (pinfunction "58/GPIO36_58") (pintype "bidirectional"))
      (node (ref "D13") (pin "C") (pinfunction "C_C") (pintype "passive"))
      (node (ref "D14") (pin "C") (pinfunction "C_C") (pintype "passive"))
      (node (ref "D15") (pin "C") (pinfunction "C_C") (pintype "passive"))
      (node (ref "D16") (pin "C") (pinfunction "C_C") (pintype "passive"))
      (node (ref "D18") (pin "C") (pinfunction "C_C") (pintype "passive"))
    )
    (net (code "112") (name "ROW_3") (class "Default")
      (node (ref "$$PCB100") (pin "54") (pinfunction "54/GPIO35_54") (pintype "bidirectional"))
      (node (ref "D19") (pin "C") (pinfunction "C_C") (pintype "passive"))
      (node (ref "D20") (pin "C") (pinfunction "C_C") (pintype "passive"))
      (node (ref "D21") (pin "C") (pinfunction "C_C") (pintype "passive"))
      (node (ref "D22") (pin "C") (pinfunction "C_C") (pintype "passive"))
      (node (ref "D23") (pin "C") (pinfunction "C_C") (pintype "passive"))
      (node (ref "D24") (pin "C") (pinfunction "C_C") (pintype "passive"))
    )
    (net (code "113") (name "ROW_4") (class "Default")
      (node (ref "$$PCB100") (pin "52") (pinfunction "52/GPIO34_52") (pintype "bidirectional"))
      (node (ref "D25") (pin "C") (pinfunction "C_C") (pintype "passive"))
      (node (ref "D26") (pin "C") (pinfunction "C_C") (pintype "passive"))
      (node (ref "D27") (pin "C") (pinfunction "C_C") (pintype "passive"))
      (node (ref "D28") (pin "C") (pinfunction "C_C") (pintype "passive"))
      (node (ref "D29") (pin "C") (pinfunction "C_C") (pintype "passive"))
      (node (ref "D30") (pin "C") (pinfunction "C_C") (pintype "passive"))
    )
    (net (code "114") (name "ROW_5") (class "Default")
      (node (ref "$$PCB100") (pin "48") (pinfunction "48/GPIO33_48") (pintype "bidirectional"))
      (node (ref "D31") (pin "C") (pinfunction "C_C") (pintype "passive"))
      (node (ref "D32") (pin "C") (pinfunction "C_C") (pintype "passive"))
      (node (ref "D33") (pin "C") (pinfunction "C_C") (pintype "passive"))
      (node (ref "D34") (pin "C") (pinfunction "C_C") (pintype "passive"))
      (node (ref "D35") (pin "C") (pinfunction "C_C") (pintype "passive"))
      (node (ref "D36") (pin "C") (pinfunction "C_C") (pintype "passive"))
    )
    (net (code "115") (name "ROW_6") (class "Default")
      (node (ref "$$PCB100") (pin "46") (pinfunction "46/GPIO32_46") (pintype "bidirectional"))
      (node (ref "D37") (pin "C") (pinfunction "C_C") (pintype "passive"))
      (node (ref "D38") (pin "C") (pinfunction "C_C") (pintype "passive"))
      (node (ref "D39") (pin "C") (pinfunction "C_C") (pintype "passive"))
      (node (ref "D40") (pin "C") (pinfunction "C_C") (pintype "passive"))
      (node (ref "D41") (pin "C") (pinfunction "C_C") (pintype "passive"))
      (node (ref "D42") (pin "C") (pinfunction "C_C") (pintype "passive"))
    )
    (net (code "116") (name "ROW_7") (class "Default")
      (node (ref "$$PCB100") (pin "36") (pinfunction "36/GPIO31_36") (pintype "bidirectional"))
      (node (ref "D43") (pin "C") (pinfunction "C_C") (pintype "passive"))
      (node (ref "D44") (pin "C") (pinfunction "C_C") (pintype "passive"))
      (node (ref "D45") (pin "C") (pinfunction "C_C") (pintype "passive"))
      (node (ref "D46") (pin "C") (pinfunction "C_C") (pintype "passive"))
      (node (ref "D47") (pin "C") (pinfunction "C_C") (pintype "passive"))
      (node (ref "D48") (pin "C") (pinfunction "C_C") (pintype "passive"))
    )
    (net (code "117") (name "ROW_8") (class "Default")
      (node (ref "$$PCB100") (pin "64") (pinfunction "64/GPIO38_64") (pintype "bidirectional"))
      (node (ref "D49") (pin "C") (pinfunction "C_C") (pintype "passive"))
      (node (ref "D50") (pin "C") (pinfunction "C_C") (pintype "passive"))
      (node (ref "D51") (pin "C") (pinfunction "C_C") (pintype "passive"))
      (node (ref "D52") (pin "C") (pinfunction "C_C") (pintype "passive"))
      (node (ref "D53") (pin "C") (pinfunction "C_C") (pintype "passive"))
      (node (ref "D54") (pin "C") (pinfunction "C_C") (pintype "passive"))
    )
    (net (code "118") (name "ROW_9") (class "Default")
      (node (ref "$$PCB100") (pin "5") (pinfunction "5/GPIO1_5") (pintype "bidirectional"))
      (node (ref "D55") (pin "C") (pinfunction "C_C") (pintype "passive"))
      (node (ref "D56") (pin "C") (pinfunction "C_C") (pintype "passive"))
      (node (ref "D57") (pin "C") (pinfunction "C_C") (pintype "passive"))
      (node (ref "D58") (pin "C") (pinfunction "C_C") (pintype "passive"))
      (node (ref "D59") (pin "C") (pinfunction "C_C") (pintype "passive"))
      (node (ref "D60") (pin "C") (pinfunction "C_C") (pintype "passive"))
    )
    (net (code "119") (name "RT_CS_3V") (class "Default")
      (node (ref "$$PCB100") (pin "23") (pinfunction "23/GPIO7_23") (pintype "bidirectional"))
      (node (ref "R8") (pin "2") (pinfunction "2_2") (pintype "passive"))
      (node (ref "UTSC") (pin "5") (pinfunction "SDAT_5") (pintype "bidirectional"))
    )
    (net (code "120") (name "RT_INT") (class "Default")
      (node (ref "$$PCB100") (pin "81") (pinfunction "81/GPIO24_81") (pintype "bidirectional"))
      (node (ref "R9") (pin "1") (pinfunction "1_1") (pintype "passive"))
      (node (ref "UTSC") (pin "2") (pinfunction "INTERRUPT_2") (pintype "bidirectional"))
    )
    (net (code "121") (name "SCLK") (class "Default")
      (node (ref "$$PCB100") (pin "35") (pinfunction "35/GPIO11_35") (pintype "bidirectional"))
      (node (ref "R17") (pin "2") (pinfunction "2_2") (pintype "passive"))
      (node (ref "TFT1") (pin "37") (pinfunction "RS_SCL_37") (pintype "bidirectional"))
      (node (ref "UTSC") (pin "4") (pinfunction "SCLK_4") (pintype "bidirectional"))
    )
    (net (code "122") (name "TFT_3V3") (class "Default")
      (node (ref "R10") (pin "2") (pinfunction "2_2") (pintype "passive"))
      (node (ref "R11") (pin "1") (pinfunction "1_1") (pintype "passive"))
      (node (ref "R13") (pin "2") (pinfunction "2_2") (pintype "passive"))
      (node (ref "R14") (pin "2") (pinfunction "2_2") (pintype "passive"))
      (node (ref "R15") (pin "2") (pinfunction "2_2") (pintype "passive"))
      (node (ref "R16") (pin "2") (pinfunction "2_2") (pintype "passive"))
      (node (ref "R17") (pin "1") (pinfunction "1_1") (pintype "passive"))
      (node (ref "R18") (pin "1") (pinfunction "1_1") (pintype "passive"))
      (node (ref "R8") (pin "1") (pinfunction "1_1") (pintype "passive"))
      (node (ref "TFT1") (pin "40") (pinfunction "IOVCC_40") (pintype "bidirectional"))
      (node (ref "TFT1") (pin "41") (pinfunction "IOVCC_41") (pintype "bidirectional"))
      (node (ref "TFT1") (pin "42") (pinfunction "VCI_42") (pintype "bidirectional"))
      (node (ref "TFT1") (pin "7") (pinfunction "IM1_7") (pintype "bidirectional"))
      (node (ref "TFT1") (pin "8") (pinfunction "IM2_8") (pintype "bidirectional"))
      (node (ref "TFT1") (pin "9") (pinfunction "IM3_9") (pintype "bidirectional"))
      (node (ref "U1") (pin "5") (pinfunction "OUT_5") (pintype "bidirectional"))
      (node (ref "U4") (pin "3") (pinfunction "VCC_3") (pintype "power_in"))
      (node (ref "UTSC") (pin "14") (pinfunction "VIO_14") (pintype "bidirectional"))
      (node (ref "UTSC") (pin "6") (pinfunction "VCC_6") (pintype "bidirectional"))
      (node (ref "UTSC") (pin "9") (pinfunction "IN1/GPIO-1/MODE_9") (pintype "bidirectional"))
    )
    (net (code "123") (name "TFT_CS_3V") (class "Default")
      (node (ref "$$PCB100") (pin "27") (pinfunction "27/GPIO8_27") (pintype "bidirectional"))
      (node (ref "TFT1") (pin "38") (pinfunction "/CS_38") (pintype "bidirectional"))
    )
    (net (code "124") (name "TFT_DC_3V") (class "Default")
      (node (ref "$$PCB100") (pin "83") (pinfunction "83/GPIO25_83") (pintype "bidirectional"))
      (node (ref "TFT1") (pin "36") (pinfunction "/WR_RS_36") (pintype "bidirectional"))
    )
    (net (code "125") (name "USB_DM") (class "Default")
      (node (ref "$$PCB100") (pin "165") (pinfunction "165/USB_DP**_165") (pintype "bidirectional"))
      (node (ref "J12") (pin "2") (pinfunction "2_2") (pintype "passive"))
    )
    (net (code "126") (name "USB_DP") (class "Default")
      (node (ref "$$PCB100") (pin "167") (pinfunction "167/USB_DM**_167") (pintype "bidirectional"))
      (node (ref "J12") (pin "3") (pinfunction "3_3") (pintype "passive"))
    )
    (net (code "127") (name "VBUSA") (class "Default")
      (node (ref "C23") (pin "1") (pinfunction "1_1") (pintype "passive"))
      (node (ref "C24") (pin "1") (pinfunction "1_1") (pintype "passive"))
      (node (ref "J12") (pin "1") (pinfunction "1_1") (pintype "passive"))
      (node (ref "J9") (pin "1") (pinfunction "1_1") (pintype "passive"))
    )
    (net (code "128") (name "X+") (class "Default")
      (node (ref "TFT1") (pin "45") (pinfunction "TP_SDA_45") (pintype "bidirectional"))
      (node (ref "UTSC") (pin "13") (pinfunction "X+_13") (pintype "bidirectional"))
    )
    (net (code "129") (name "X-") (class "Default")
      (node (ref "TFT1") (pin "44") (pinfunction "TP_SCK_44") (pintype "bidirectional"))
      (node (ref "UTSC") (pin "16") (pinfunction "X-_16") (pintype "bidirectional"))
    )
    (net (code "130") (name "Y+") (class "Default")
      (node (ref "TFT1") (pin "46") (pinfunction "TP_IRQ_46") (pintype "bidirectional"))
      (node (ref "UTSC") (pin "15") (pinfunction "Y+_15") (pintype "bidirectional"))
    )
    (net (code "131") (name "Y-") (class "Default")
      (node (ref "TFT1") (pin "47") (pinfunction "TP_RES_47") (pintype "bidirectional"))
      (node (ref "UTSC") (pin "1") (pinfunction "Y-_1") (pintype "bidirectional"))
    )
    (net (code "132") (name "unconnected-($$PCB100-1{slash}GND-Pad1)") (class "Default")
      (node (ref "$$PCB100") (pin "1") (pinfunction "1/GND_1") (pintype "bidirectional"))
    )
    (net (code "133") (name "unconnected-($$PCB100-4{slash}NC-Pad4)") (class "Default")
      (node (ref "$$PCB100") (pin "4") (pinfunction "4/NC_4") (pintype "bidirectional"))
    )
    (net (code "134") (name "unconnected-($$PCB100-6{slash}NC-Pad6)") (class "Default")
      (node (ref "$$PCB100") (pin "6") (pinfunction "6/NC_6") (pintype "bidirectional"))
    )
    (net (code "135") (name "unconnected-($$PCB100-7{slash}GND-Pad7)") (class "Default")
      (node (ref "$$PCB100") (pin "7") (pinfunction "7/GND_7") (pintype "bidirectional"))
    )
    (net (code "136") (name "unconnected-($$PCB100-8{slash}NC-Pad8)") (class "Default")
      (node (ref "$$PCB100") (pin "8") (pinfunction "8/NC_8") (pintype "bidirectional"))
    )
    (net (code "137") (name "unconnected-($$PCB100-9{slash}GPIO2-Pad9)") (class "Default")
      (node (ref "$$PCB100") (pin "9") (pinfunction "9/GPIO2_9") (pintype "bidirectional"))
    )
    (net (code "138") (name "unconnected-($$PCB100-10{slash}NC-Pad10)") (class "Default")
      (node (ref "$$PCB100") (pin "10") (pinfunction "10/NC_10") (pintype "bidirectional"))
    )
    (net (code "139") (name "unconnected-($$PCB100-11{slash}GPIO3-Pad11)") (class "Default")
      (node (ref "$$PCB100") (pin "11") (pinfunction "11/GPIO3_11") (pintype "bidirectional"))
    )
    (net (code "140") (name "unconnected-($$PCB100-12{slash}NC-Pad12)") (class "Default")
      (node (ref "$$PCB100") (pin "12") (pinfunction "12/NC_12") (pintype "bidirectional"))
    )
    (net (code "141") (name "unconnected-($$PCB100-13{slash}GND-Pad13)") (class "Default")
      (node (ref "$$PCB100") (pin "13") (pinfunction "13/GND_13") (pintype "bidirectional"))
    )
    (net (code "142") (name "unconnected-($$PCB100-14{slash}NC-Pad14)") (class "Default")
      (node (ref "$$PCB100") (pin "14") (pinfunction "14/NC_14") (pintype "bidirectional"))
    )
    (net (code "143") (name "unconnected-($$PCB100-15{slash}GPIO4-Pad15)") (class "Default")
      (node (ref "$$PCB100") (pin "15") (pinfunction "15/GPIO4_15") (pintype "bidirectional"))
    )
    (net (code "144") (name "unconnected-($$PCB100-16{slash}NC-Pad16)") (class "Default")
      (node (ref "$$PCB100") (pin "16") (pinfunction "16/NC_16") (pintype "bidirectional"))
    )
    (net (code "145") (name "unconnected-($$PCB100-17{slash}GPIO5-Pad17)") (class "Default")
      (node (ref "$$PCB100") (pin "17") (pinfunction "17/GPIO5_17") (pintype "bidirectional"))
    )
    (net (code "146") (name "unconnected-($$PCB100-18{slash}NC-Pad18)") (class "Default")
      (node (ref "$$PCB100") (pin "18") (pinfunction "18/NC_18") (pintype "bidirectional"))
    )
    (net (code "147") (name "unconnected-($$PCB100-19{slash}GND-Pad19)") (class "Default")
      (node (ref "$$PCB100") (pin "19") (pinfunction "19/GND_19") (pintype "bidirectional"))
    )
    (net (code "148") (name "unconnected-($$PCB100-20{slash}NC-Pad20)") (class "Default")
      (node (ref "$$PCB100") (pin "20") (pinfunction "20/NC_20") (pintype "bidirectional"))
    )
    (net (code "149") (name "unconnected-($$PCB100-21{slash}GPIO6-Pad21)") (class "Default")
      (node (ref "$$PCB100") (pin "21") (pinfunction "21/GPIO6_21") (pintype "bidirectional"))
    )
    (net (code "150") (name "unconnected-($$PCB100-22{slash}NC-Pad22)") (class "Default")
      (node (ref "$$PCB100") (pin "22") (pinfunction "22/NC_22") (pintype "bidirectional"))
    )
    (net (code "151") (name "unconnected-($$PCB100-24{slash}NC-Pad24)") (class "Default")
      (node (ref "$$PCB100") (pin "24") (pinfunction "24/NC_24") (pintype "bidirectional"))
    )
    (net (code "152") (name "unconnected-($$PCB100-25{slash}GND-Pad25)") (class "Default")
      (node (ref "$$PCB100") (pin "25") (pinfunction "25/GND_25") (pintype "bidirectional"))
    )
    (net (code "153") (name "unconnected-($$PCB100-26{slash}GND-Pad26)") (class "Default")
      (node (ref "$$PCB100") (pin "26") (pinfunction "26/GND_26") (pintype "bidirectional"))
    )
    (net (code "154") (name "unconnected-($$PCB100-31{slash}GND-Pad31)") (class "Default")
      (node (ref "$$PCB100") (pin "31") (pinfunction "31/GND_31") (pintype "bidirectional"))
    )
    (net (code "155") (name "unconnected-($$PCB100-32{slash}GND-Pad32)") (class "Default")
      (node (ref "$$PCB100") (pin "32") (pinfunction "32/GND_32") (pintype "bidirectional"))
    )
    (net (code "156") (name "unconnected-($$PCB100-34{slash}GPIO30-Pad34)") (class "Default")
      (node (ref "$$PCB100") (pin "34") (pinfunction "34/GPIO30_34") (pintype "bidirectional"))
    )
    (net (code "157") (name "unconnected-($$PCB100-37{slash}GND-Pad37)") (class "Default")
      (node (ref "$$PCB100") (pin "37") (pinfunction "37/GND_37") (pintype "bidirectional"))
    )
    (net (code "158") (name "unconnected-($$PCB100-38{slash}GND-Pad38)") (class "Default")
      (node (ref "$$PCB100") (pin "38") (pinfunction "38/GND_38") (pintype "bidirectional"))
    )
    (net (code "159") (name "unconnected-($$PCB100-39{slash}GPIO0-27_VREF-Pad39)") (class "Default")
      (node (ref "$$PCB100") (pin "39") (pinfunction "39/GPIO0-27_VREF_39") (pintype "bidirectional"))
    )
    (net (code "160") (name "unconnected-($$PCB100-41{slash}GPIO28-45_VREF-Pad41)") (class "Default")
      (node (ref "$$PCB100") (pin "41") (pinfunction "41/GPIO28-45_VREF_41") (pintype "bidirectional"))
    )
    (net (code "161") (name "unconnected-($$PCB100-43{slash}GND-Pad43)") (class "Default")
      (node (ref "$$PCB100") (pin "43") (pinfunction "43/GND_43") (pintype "bidirectional"))
    )
    (net (code "162") (name "unconnected-($$PCB100-44{slash}GND-Pad44)") (class "Default")
      (node (ref "$$PCB100") (pin "44") (pinfunction "44/GND_44") (pintype "bidirectional"))
    )
    (net (code "163") (name "unconnected-($$PCB100-45{slash}GPIO12-Pad45)") (class "Default")
      (node (ref "$$PCB100") (pin "45") (pinfunction "45/GPIO12_45") (pintype "bidirectional"))
    )
    (net (code "164") (name "unconnected-($$PCB100-47{slash}GPIO13-Pad47)") (class "Default")
      (node (ref "$$PCB100") (pin "47") (pinfunction "47/GPIO13_47") (pintype "bidirectional"))
    )
    (net (code "165") (name "unconnected-($$PCB100-49{slash}GND-Pad49)") (class "Default")
      (node (ref "$$PCB100") (pin "49") (pinfunction "49/GND_49") (pintype "bidirectional"))
    )
    (net (code "166") (name "unconnected-($$PCB100-50{slash}GND-Pad50)") (class "Default")
      (node (ref "$$PCB100") (pin "50") (pinfunction "50/GND_50") (pintype "bidirectional"))
    )
    (net (code "167") (name "unconnected-($$PCB100-51{slash}GPIO14-Pad51)") (class "Default")
      (node (ref "$$PCB100") (pin "51") (pinfunction "51/GPIO14_51") (pintype "bidirectional"))
    )
    (net (code "168") (name "unconnected-($$PCB100-53{slash}GPIO15-Pad53)") (class "Default")
      (node (ref "$$PCB100") (pin "53") (pinfunction "53/GPIO15_53") (pintype "bidirectional"))
    )
    (net (code "169") (name "unconnected-($$PCB100-55{slash}GND-Pad55)") (class "Default")
      (node (ref "$$PCB100") (pin "55") (pinfunction "55/GND_55") (pintype "bidirectional"))
    )
    (net (code "170") (name "unconnected-($$PCB100-56{slash}GND-Pad56)") (class "Default")
      (node (ref "$$PCB100") (pin "56") (pinfunction "56/GND_56") (pintype "bidirectional"))
    )
    (net (code "171") (name "unconnected-($$PCB100-57{slash}GPIO16-Pad57)") (class "Default")
      (node (ref "$$PCB100") (pin "57") (pinfunction "57/GPIO16_57") (pintype "bidirectional"))
    )
    (net (code "172") (name "unconnected-($$PCB100-59{slash}GPIO17-Pad59)") (class "Default")
      (node (ref "$$PCB100") (pin "59") (pinfunction "59/GPIO17_59") (pintype "bidirectional"))
    )
    (net (code "173") (name "unconnected-($$PCB100-61{slash}GND-Pad61)") (class "Default")
      (node (ref "$$PCB100") (pin "61") (pinfunction "61/GND_61") (pintype "bidirectional"))
    )
    (net (code "174") (name "unconnected-($$PCB100-62{slash}GND-Pad62)") (class "Default")
      (node (ref "$$PCB100") (pin "62") (pinfunction "62/GND_62") (pintype "bidirectional"))
    )
    (net (code "175") (name "unconnected-($$PCB100-63{slash}GPIO18-Pad63)") (class "Default")
      (node (ref "$$PCB100") (pin "63") (pinfunction "63/GPIO18_63") (pintype "bidirectional"))
    )
    (net (code "176") (name "unconnected-($$PCB100-65{slash}GPIO19-Pad65)") (class "Default")
      (node (ref "$$PCB100") (pin "65") (pinfunction "65/GPIO19_65") (pintype "bidirectional"))
    )
    (net (code "177") (name "unconnected-($$PCB100-67{slash}GND-Pad67)") (class "Default")
      (node (ref "$$PCB100") (pin "67") (pinfunction "67/GND_67") (pintype "bidirectional"))
    )
    (net (code "178") (name "unconnected-($$PCB100-68{slash}GND-Pad68)") (class "Default")
      (node (ref "$$PCB100") (pin "68") (pinfunction "68/GND_68") (pintype "bidirectional"))
    )
    (net (code "179") (name "unconnected-($$PCB100-73{slash}GND-Pad73)") (class "Default")
      (node (ref "$$PCB100") (pin "73") (pinfunction "73/GND_73") (pintype "bidirectional"))
    )
    (net (code "180") (name "unconnected-($$PCB100-74{slash}GND-Pad74)") (class "Default")
      (node (ref "$$PCB100") (pin "74") (pinfunction "74/GND_74") (pintype "bidirectional"))
    )
    (net (code "181") (name "unconnected-($$PCB100-79{slash}GND-Pad79)") (class "Default")
      (node (ref "$$PCB100") (pin "79") (pinfunction "79/GND_79") (pintype "bidirectional"))
    )
    (net (code "182") (name "unconnected-($$PCB100-80{slash}GND-Pad80)") (class "Default")
      (node (ref "$$PCB100") (pin "80") (pinfunction "80/GND_80") (pintype "bidirectional"))
    )
    (net (code "183") (name "unconnected-($$PCB100-85{slash}GND-Pad85)") (class "Default")
      (node (ref "$$PCB100") (pin "85") (pinfunction "85/GND_85") (pintype "bidirectional"))
    )
    (net (code "184") (name "unconnected-($$PCB100-86{slash}GND-Pad86)") (class "Default")
      (node (ref "$$PCB100") (pin "86") (pinfunction "86/GND_86") (pintype "bidirectional"))
    )
    (net (code "185") (name "unconnected-($$PCB100-90{slash}GPIO47_1V8-Pad90)") (class "Default")
      (node (ref "$$PCB100") (pin "90") (pinfunction "90/GPIO47_1V8_90") (pintype "bidirectional"))
    )
    (net (code "186") (name "unconnected-($$PCB100-91{slash}GND-Pad91)") (class "Default")
      (node (ref "$$PCB100") (pin "91") (pinfunction "91/GND_91") (pintype "bidirectional"))
    )
    (net (code "187") (name "unconnected-($$PCB100-92{slash}GND-Pad92)") (class "Default")
      (node (ref "$$PCB100") (pin "92") (pinfunction "92/GND_92") (pintype "bidirectional"))
    )
    (net (code "188") (name "unconnected-($$PCB100-93{slash}DSI0_DN1*-Pad93)") (class "Default")
      (node (ref "$$PCB100") (pin "93") (pinfunction "93/DSI0_DN1*_93") (pintype "bidirectional"))
    )
    (net (code "189") (name "unconnected-($$PCB100-94{slash}DSI1_DP0*-Pad94)") (class "Default")
      (node (ref "$$PCB100") (pin "94") (pinfunction "94/DSI1_DP0*_94") (pintype "bidirectional"))
    )
    (net (code "190") (name "unconnected-($$PCB100-95{slash}DSI0_DP1*-Pad95)") (class "Default")
      (node (ref "$$PCB100") (pin "95") (pinfunction "95/DSI0_DP1*_95") (pintype "bidirectional"))
    )
    (net (code "191") (name "unconnected-($$PCB100-96{slash}DSI1_DN0*-Pad96)") (class "Default")
      (node (ref "$$PCB100") (pin "96") (pinfunction "96/DSI1_DN0*_96") (pintype "bidirectional"))
    )
    (net (code "192") (name "unconnected-($$PCB100-97{slash}GND-Pad97)") (class "Default")
      (node (ref "$$PCB100") (pin "97") (pinfunction "97/GND_97") (pintype "bidirectional"))
    )
    (net (code "193") (name "unconnected-($$PCB100-98{slash}GND-Pad98)") (class "Default")
      (node (ref "$$PCB100") (pin "98") (pinfunction "98/GND_98") (pintype "bidirectional"))
    )
    (net (code "194") (name "unconnected-($$PCB100-99{slash}DSI0_DN0*-Pad99)") (class "Default")
      (node (ref "$$PCB100") (pin "99") (pinfunction "99/DSI0_DN0*_99") (pintype "bidirectional"))
    )
    (net (code "195") (name "unconnected-($$PCB100-100{slash}DSI1CP*-Pad100)") (class "Default")
      (node (ref "$$PCB100") (pin "100") (pinfunction "100/DSI1CP*_100") (pintype "bidirectional"))
    )
    (net (code "196") (name "unconnected-($$PCB100-101{slash}DSI0_DP0*-Pad101)") (class "Default")
      (node (ref "$$PCB100") (pin "101") (pinfunction "101/DSI0_DP0*_101") (pintype "bidirectional"))
    )
    (net (code "197") (name "unconnected-($$PCB100-102{slash}DSI1CN*-Pad102)") (class "Default")
      (node (ref "$$PCB100") (pin "102") (pinfunction "102/DSI1CN*_102") (pintype "bidirectional"))
    )
    (net (code "198") (name "unconnected-($$PCB100-103{slash}GND-Pad103)") (class "Default")
      (node (ref "$$PCB100") (pin "103") (pinfunction "103/GND_103") (pintype "bidirectional"))
    )
    (net (code "199") (name "unconnected-($$PCB100-104{slash}GND-Pad104)") (class "Default")
      (node (ref "$$PCB100") (pin "104") (pinfunction "104/GND_104") (pintype "bidirectional"))
    )
    (net (code "200") (name "unconnected-($$PCB100-105{slash}DSI0_CN*-Pad105)") (class "Default")
      (node (ref "$$PCB100") (pin "105") (pinfunction "105/DSI0_CN*_105") (pintype "bidirectional"))
    )
    (net (code "201") (name "unconnected-($$PCB100-106{slash}DSI1_DP3*-Pad106)") (class "Default")
      (node (ref "$$PCB100") (pin "106") (pinfunction "106/DSI1_DP3*_106") (pintype "bidirectional"))
    )
    (net (code "202") (name "unconnected-($$PCB100-107{slash}DSI0_CP*-Pad107)") (class "Default")
      (node (ref "$$PCB100") (pin "107") (pinfunction "107/DSI0_CP*_107") (pintype "bidirectional"))
    )
    (net (code "203") (name "unconnected-($$PCB100-108{slash}DSI1_DN3*-Pad108)") (class "Default")
      (node (ref "$$PCB100") (pin "108") (pinfunction "108/DSI1_DN3*_108") (pintype "bidirectional"))
    )
    (net (code "204") (name "unconnected-($$PCB100-109{slash}GND-Pad109)") (class "Default")
      (node (ref "$$PCB100") (pin "109") (pinfunction "109/GND_109") (pintype "bidirectional"))
    )
    (net (code "205") (name "unconnected-($$PCB100-110{slash}GND-Pad110)") (class "Default")
      (node (ref "$$PCB100") (pin "110") (pinfunction "110/GND_110") (pintype "bidirectional"))
    )
    (net (code "206") (name "unconnected-($$PCB100-111{slash}HDMI_CK_N*-Pad111)") (class "Default")
      (node (ref "$$PCB100") (pin "111") (pinfunction "111/HDMI_CK_N*_111") (pintype "bidirectional"))
    )
    (net (code "207") (name "unconnected-($$PCB100-112{slash}DSI1_DP2*-Pad112)") (class "Default")
      (node (ref "$$PCB100") (pin "112") (pinfunction "112/DSI1_DP2*_112") (pintype "bidirectional"))
    )
    (net (code "208") (name "unconnected-($$PCB100-113{slash}HDMI_CK_P*-Pad113)") (class "Default")
      (node (ref "$$PCB100") (pin "113") (pinfunction "113/HDMI_CK_P*_113") (pintype "bidirectional"))
    )
    (net (code "209") (name "unconnected-($$PCB100-114{slash}DSI1_DN2*-Pad114)") (class "Default")
      (node (ref "$$PCB100") (pin "114") (pinfunction "114/DSI1_DN2*_114") (pintype "bidirectional"))
    )
    (net (code "210") (name "unconnected-($$PCB100-115{slash}GND-Pad115)") (class "Default")
      (node (ref "$$PCB100") (pin "115") (pinfunction "115/GND_115") (pintype "bidirectional"))
    )
    (net (code "211") (name "unconnected-($$PCB100-116{slash}GND-Pad116)") (class "Default")
      (node (ref "$$PCB100") (pin "116") (pinfunction "116/GND_116") (pintype "bidirectional"))
    )
    (net (code "212") (name "unconnected-($$PCB100-117{slash}HDMI_D0_N*-Pad117)") (class "Default")
      (node (ref "$$PCB100") (pin "117") (pinfunction "117/HDMI_D0_N*_117") (pintype "bidirectional"))
    )
    (net (code "213") (name "unconnected-($$PCB100-118{slash}DSI1_DP1*-Pad118)") (class "Default")
      (node (ref "$$PCB100") (pin "118") (pinfunction "118/DSI1_DP1*_118") (pintype "bidirectional"))
    )
    (net (code "214") (name "unconnected-($$PCB100-119{slash}HDMI_D0_P*-Pad119)") (class "Default")
      (node (ref "$$PCB100") (pin "119") (pinfunction "119/HDMI_D0_P*_119") (pintype "bidirectional"))
    )
    (net (code "215") (name "unconnected-($$PCB100-120{slash}DSI1_DN1*-Pad120)") (class "Default")
      (node (ref "$$PCB100") (pin "120") (pinfunction "120/DSI1_DN1*_120") (pintype "bidirectional"))
    )
    (net (code "216") (name "unconnected-($$PCB100-121{slash}GND-Pad121)") (class "Default")
      (node (ref "$$PCB100") (pin "121") (pinfunction "121/GND_121") (pintype "bidirectional"))
    )
    (net (code "217") (name "unconnected-($$PCB100-122{slash}GND-Pad122)") (class "Default")
      (node (ref "$$PCB100") (pin "122") (pinfunction "122/GND_122") (pintype "bidirectional"))
    )
    (net (code "218") (name "unconnected-($$PCB100-123{slash}HDMI_D1_N*-Pad123)") (class "Default")
      (node (ref "$$PCB100") (pin "123") (pinfunction "123/HDMI_D1_N*_123") (pintype "bidirectional"))
    )
    (net (code "219") (name "unconnected-($$PCB100-124{slash}NC-Pad124)") (class "Default")
      (node (ref "$$PCB100") (pin "124") (pinfunction "124/NC_124") (pintype "bidirectional"))
    )
    (net (code "220") (name "unconnected-($$PCB100-125{slash}HDMI_D1_P*-Pad125)") (class "Default")
      (node (ref "$$PCB100") (pin "125") (pinfunction "125/HDMI_D1_P*_125") (pintype "bidirectional"))
    )
    (net (code "221") (name "unconnected-($$PCB100-126{slash}NC-Pad126)") (class "Default")
      (node (ref "$$PCB100") (pin "126") (pinfunction "126/NC_126") (pintype "bidirectional"))
    )
    (net (code "222") (name "unconnected-($$PCB100-127{slash}GND-Pad127)") (class "Default")
      (node (ref "$$PCB100") (pin "127") (pinfunction "127/GND_127") (pintype "bidirectional"))
    )
    (net (code "223") (name "unconnected-($$PCB100-128{slash}NC-Pad128)") (class "Default")
      (node (ref "$$PCB100") (pin "128") (pinfunction "128/NC_128") (pintype "bidirectional"))
    )
    (net (code "224") (name "unconnected-($$PCB100-129{slash}HDMI_D2_N*-Pad129)") (class "Default")
      (node (ref "$$PCB100") (pin "129") (pinfunction "129/HDMI_D2_N*_129") (pintype "bidirectional"))
    )
    (net (code "225") (name "unconnected-($$PCB100-130{slash}NC-Pad130)") (class "Default")
      (node (ref "$$PCB100") (pin "130") (pinfunction "130/NC_130") (pintype "bidirectional"))
    )
    (net (code "226") (name "unconnected-($$PCB100-131{slash}HDMI_D2_P*-Pad131)") (class "Default")
      (node (ref "$$PCB100") (pin "131") (pinfunction "131/HDMI_D2_P*_131") (pintype "bidirectional"))
    )
    (net (code "227") (name "unconnected-($$PCB100-132{slash}NC-Pad132)") (class "Default")
      (node (ref "$$PCB100") (pin "132") (pinfunction "132/NC_132") (pintype "bidirectional"))
    )
    (net (code "228") (name "unconnected-($$PCB100-133{slash}GND-Pad133)") (class "Default")
      (node (ref "$$PCB100") (pin "133") (pinfunction "133/GND_133") (pintype "bidirectional"))
    )
    (net (code "229") (name "unconnected-($$PCB100-135{slash}CAM1_DP3*-Pad135)") (class "Default")
      (node (ref "$$PCB100") (pin "135") (pinfunction "135/CAM1_DP3*_135") (pintype "bidirectional"))
    )
    (net (code "230") (name "unconnected-($$PCB100-136{slash}CAM0_DP0*-Pad136)") (class "Default")
      (node (ref "$$PCB100") (pin "136") (pinfunction "136/CAM0_DP0*_136") (pintype "bidirectional"))
    )
    (net (code "231") (name "unconnected-($$PCB100-137{slash}CAM1_DN3*-Pad137)") (class "Default")
      (node (ref "$$PCB100") (pin "137") (pinfunction "137/CAM1_DN3*_137") (pintype "bidirectional"))
    )
    (net (code "232") (name "unconnected-($$PCB100-138{slash}CAM0_DN0*-Pad138)") (class "Default")
      (node (ref "$$PCB100") (pin "138") (pinfunction "138/CAM0_DN0*_138") (pintype "bidirectional"))
    )
    (net (code "233") (name "unconnected-($$PCB100-139{slash}GND-Pad139)") (class "Default")
      (node (ref "$$PCB100") (pin "139") (pinfunction "139/GND_139") (pintype "bidirectional"))
    )
    (net (code "234") (name "unconnected-($$PCB100-140{slash}GND-Pad140)") (class "Default")
      (node (ref "$$PCB100") (pin "140") (pinfunction "140/GND_140") (pintype "bidirectional"))
    )
    (net (code "235") (name "unconnected-($$PCB100-141{slash}CAM1_DP2*-Pad141)") (class "Default")
      (node (ref "$$PCB100") (pin "141") (pinfunction "141/CAM1_DP2*_141") (pintype "bidirectional"))
    )
    (net (code "236") (name "unconnected-($$PCB100-142{slash}CAM0_CP*-Pad142)") (class "Default")
      (node (ref "$$PCB100") (pin "142") (pinfunction "142/CAM0_CP*_142") (pintype "bidirectional"))
    )
    (net (code "237") (name "unconnected-($$PCB100-143{slash}CAM1_DN2*-Pad143)") (class "Default")
      (node (ref "$$PCB100") (pin "143") (pinfunction "143/CAM1_DN2*_143") (pintype "bidirectional"))
    )
    (net (code "238") (name "unconnected-($$PCB100-144{slash}CAM0_CN*-Pad144)") (class "Default")
      (node (ref "$$PCB100") (pin "144") (pinfunction "144/CAM0_CN*_144") (pintype "bidirectional"))
    )
    (net (code "239") (name "unconnected-($$PCB100-145{slash}GND-Pad145)") (class "Default")
      (node (ref "$$PCB100") (pin "145") (pinfunction "145/GND_145") (pintype "bidirectional"))
    )
    (net (code "240") (name "unconnected-($$PCB100-146{slash}GND-Pad146)") (class "Default")
      (node (ref "$$PCB100") (pin "146") (pinfunction "146/GND_146") (pintype "bidirectional"))
    )
    (net (code "241") (name "unconnected-($$PCB100-147{slash}CAM1_CP*-Pad147)") (class "Default")
      (node (ref "$$PCB100") (pin "147") (pinfunction "147/CAM1_CP*_147") (pintype "bidirectional"))
    )
    (net (code "242") (name "unconnected-($$PCB100-148{slash}CAM0_DP1*-Pad148)") (class "Default")
      (node (ref "$$PCB100") (pin "148") (pinfunction "148/CAM0_DP1*_148") (pintype "bidirectional"))
    )
    (net (code "243") (name "unconnected-($$PCB100-149{slash}CAM1_CN*-Pad149)") (class "Default")
      (node (ref "$$PCB100") (pin "149") (pinfunction "149/CAM1_CN*_149") (pintype "bidirectional"))
    )
    (net (code "244") (name "unconnected-($$PCB100-150{slash}CAM0_DN1*-Pad150)") (class "Default")
      (node (ref "$$PCB100") (pin "150") (pinfunction "150/CAM0_DN1*_150") (pintype "bidirectional"))
    )
    (net (code "245") (name "unconnected-($$PCB100-151{slash}GND-Pad151)") (class "Default")
      (node (ref "$$PCB100") (pin "151") (pinfunction "151/GND_151") (pintype "bidirectional"))
    )
    (net (code "246") (name "unconnected-($$PCB100-152{slash}GND-Pad152)") (class "Default")
      (node (ref "$$PCB100") (pin "152") (pinfunction "152/GND_152") (pintype "bidirectional"))
    )
    (net (code "247") (name "unconnected-($$PCB100-153{slash}CAM1_DP1*-Pad153)") (class "Default")
      (node (ref "$$PCB100") (pin "153") (pinfunction "153/CAM1_DP1*_153") (pintype "bidirectional"))
    )
    (net (code "248") (name "unconnected-($$PCB100-154{slash}NC-Pad154)") (class "Default")
      (node (ref "$$PCB100") (pin "154") (pinfunction "154/NC_154") (pintype "bidirectional"))
    )
    (net (code "249") (name "unconnected-($$PCB100-155{slash}CAM1_DN1*-Pad155)") (class "Default")
      (node (ref "$$PCB100") (pin "155") (pinfunction "155/CAM1_DN1*_155") (pintype "bidirectional"))
    )
    (net (code "250") (name "unconnected-($$PCB100-156{slash}NC-Pad156)") (class "Default")
      (node (ref "$$PCB100") (pin "156") (pinfunction "156/NC_156") (pintype "bidirectional"))
    )
    (net (code "251") (name "unconnected-($$PCB100-157{slash}GND-Pad157)") (class "Default")
      (node (ref "$$PCB100") (pin "157") (pinfunction "157/GND_157") (pintype "bidirectional"))
    )
    (net (code "252") (name "unconnected-($$PCB100-158{slash}NC-Pad158)") (class "Default")
      (node (ref "$$PCB100") (pin "158") (pinfunction "158/NC_158") (pintype "bidirectional"))
    )
    (net (code "253") (name "unconnected-($$PCB100-159{slash}CAM1_DP0*-Pad159)") (class "Default")
      (node (ref "$$PCB100") (pin "159") (pinfunction "159/CAM1_DP0*_159") (pintype "bidirectional"))
    )
    (net (code "254") (name "unconnected-($$PCB100-160{slash}NC-Pad160)") (class "Default")
      (node (ref "$$PCB100") (pin "160") (pinfunction "160/NC_160") (pintype "bidirectional"))
    )
    (net (code "255") (name "unconnected-($$PCB100-161{slash}CAM1_DN0*-Pad161)") (class "Default")
      (node (ref "$$PCB100") (pin "161") (pinfunction "161/CAM1_DN0*_161") (pintype "bidirectional"))
    )
    (net (code "256") (name "unconnected-($$PCB100-162{slash}NC-Pad162)") (class "Default")
      (node (ref "$$PCB100") (pin "162") (pinfunction "162/NC_162") (pintype "bidirectional"))
    )
    (net (code "257") (name "unconnected-($$PCB100-163{slash}GND-Pad163)") (class "Default")
      (node (ref "$$PCB100") (pin "163") (pinfunction "163/GND_163") (pintype "bidirectional"))
    )
    (net (code "258") (name "unconnected-($$PCB100-164{slash}GND-Pad164)") (class "Default")
      (node (ref "$$PCB100") (pin "164") (pinfunction "164/GND_164") (pintype "bidirectional"))
    )
    (net (code "259") (name "unconnected-($$PCB100-166{slash}TVDAC-Pad166)") (class "Default")
      (node (ref "$$PCB100") (pin "166") (pinfunction "166/TVDAC_166") (pintype "bidirectional"))
    )
    (net (code "260") (name "unconnected-($$PCB100-169{slash}GND-Pad169)") (class "Default")
      (node (ref "$$PCB100") (pin "169") (pinfunction "169/GND_169") (pintype "bidirectional"))
    )
    (net (code "261") (name "unconnected-($$PCB100-170{slash}GND-Pad170)") (class "Default")
      (node (ref "$$PCB100") (pin "170") (pinfunction "170/GND_170") (pintype "bidirectional"))
    )
    (net (code "262") (name "unconnected-($$PCB100-171{slash}HDMI_CEC-Pad171)") (class "Default")
      (node (ref "$$PCB100") (pin "171") (pinfunction "171/HDMI_CEC_171") (pintype "bidirectional"))
    )
    (net (code "263") (name "unconnected-($$PCB100-172{slash}VC_TRST_N-Pad172)") (class "Default")
      (node (ref "$$PCB100") (pin "172") (pinfunction "172/VC_TRST_N_172") (pintype "bidirectional"))
    )
    (net (code "264") (name "unconnected-($$PCB100-173{slash}HDMI_SDA-Pad173)") (class "Default")
      (node (ref "$$PCB100") (pin "173") (pinfunction "173/HDMI_SDA_173") (pintype "bidirectional"))
    )
    (net (code "265") (name "unconnected-($$PCB100-174{slash}VC_TDI-Pad174)") (class "Default")
      (node (ref "$$PCB100") (pin "174") (pinfunction "174/VC_TDI_174") (pintype "bidirectional"))
    )
    (net (code "266") (name "unconnected-($$PCB100-175{slash}HDMI_SCL-Pad175)") (class "Default")
      (node (ref "$$PCB100") (pin "175") (pinfunction "175/HDMI_SCL_175") (pintype "bidirectional"))
    )
    (net (code "267") (name "unconnected-($$PCB100-176{slash}VC_TMS-Pad176)") (class "Default")
      (node (ref "$$PCB100") (pin "176") (pinfunction "176/VC_TMS_176") (pintype "bidirectional"))
    )
    (net (code "268") (name "unconnected-($$PCB100-177{slash}RUN-Pad177)") (class "Default")
      (node (ref "$$PCB100") (pin "177") (pinfunction "177/RUN_177") (pintype "bidirectional"))
    )
    (net (code "269") (name "unconnected-($$PCB100-178{slash}VC_TDO-Pad178)") (class "Default")
      (node (ref "$$PCB100") (pin "178") (pinfunction "178/VC_TDO_178") (pintype "bidirectional"))
    )
    (net (code "270") (name "unconnected-($$PCB100-179{slash}VDD_CORE-Pad179)") (class "Default")
      (node (ref "$$PCB100") (pin "179") (pinfunction "179/VDD_CORE_179") (pintype "bidirectional"))
    )
    (net (code "271") (name "unconnected-($$PCB100-180{slash}VC_TCK-Pad180)") (class "Default")
      (node (ref "$$PCB100") (pin "180") (pinfunction "180/VC_TCK_180") (pintype "bidirectional"))
    )
    (net (code "272") (name "unconnected-($$PCB100-181{slash}GND-Pad181)") (class "Default")
      (node (ref "$$PCB100") (pin "181") (pinfunction "181/GND_181") (pintype "bidirectional"))
    )
    (net (code "273") (name "unconnected-($$PCB100-182{slash}GND-Pad182)") (class "Default")
      (node (ref "$$PCB100") (pin "182") (pinfunction "182/GND_182") (pintype "bidirectional"))
    )
    (net (code "274") (name "unconnected-($$PCB100-187{slash}GND-Pad187)") (class "Default")
      (node (ref "$$PCB100") (pin "187") (pinfunction "187/GND_187") (pintype "bidirectional"))
    )
    (net (code "275") (name "unconnected-($$PCB100-188{slash}GND-Pad188)") (class "Default")
      (node (ref "$$PCB100") (pin "188") (pinfunction "188/GND_188") (pintype "bidirectional"))
    )
    (net (code "276") (name "unconnected-($$PCB100-195{slash}GND-Pad195)") (class "Default")
      (node (ref "$$PCB100") (pin "195") (pinfunction "195/GND_195") (pintype "bidirectional"))
    )
    (net (code "277") (name "unconnected-($$PCB100-196{slash}GND-Pad196)") (class "Default")
      (node (ref "$$PCB100") (pin "196") (pinfunction "196/GND_196") (pintype "bidirectional"))
    )
    (net (code "278") (name "unconnected-(B1-P1-PadA')") (class "Default")
      (node (ref "B1") (pin "A'") (pinfunction "P1_A'") (pintype "passive"))
    )
    (net (code "279") (name "unconnected-(B1-S1-PadB')") (class "Default")
      (node (ref "B1") (pin "B'") (pinfunction "S1_B'") (pintype "passive"))
    )
    (net (code "280") (name "unconnected-(B2-P1-PadA')") (class "Default")
      (node (ref "B2") (pin "A'") (pinfunction "P1_A'") (pintype "passive"))
    )
    (net (code "281") (name "unconnected-(B2-S1-PadB')") (class "Default")
      (node (ref "B2") (pin "B'") (pinfunction "S1_B'") (pintype "passive"))
    )
    (net (code "282") (name "unconnected-(B3-P1-PadA')") (class "Default")
      (node (ref "B3") (pin "A'") (pinfunction "P1_A'") (pintype "passive"))
    )
    (net (code "283") (name "unconnected-(B3-S1-PadB')") (class "Default")
      (node (ref "B3") (pin "B'") (pinfunction "S1_B'") (pintype "passive"))
    )
    (net (code "284") (name "unconnected-(B4-P1-PadA')") (class "Default")
      (node (ref "B4") (pin "A'") (pinfunction "P1_A'") (pintype "passive"))
    )
    (net (code "285") (name "unconnected-(B4-S1-PadB')") (class "Default")
      (node (ref "B4") (pin "B'") (pinfunction "S1_B'") (pintype "passive"))
    )
    (net (code "286") (name "unconnected-(B5-P1-PadA')") (class "Default")
      (node (ref "B5") (pin "A'") (pinfunction "P1_A'") (pintype "passive"))
    )
    (net (code "287") (name "unconnected-(B5-S1-PadB')") (class "Default")
      (node (ref "B5") (pin "B'") (pinfunction "S1_B'") (pintype "passive"))
    )
    (net (code "288") (name "unconnected-(B6-P1-PadA')") (class "Default")
      (node (ref "B6") (pin "A'") (pinfunction "P1_A'") (pintype "passive"))
    )
    (net (code "289") (name "unconnected-(B6-S1-PadB')") (class "Default")
      (node (ref "B6") (pin "B'") (pinfunction "S1_B'") (pintype "passive"))
    )
    (net (code "290") (name "unconnected-(B7-P1-PadA')") (class "Default")
      (node (ref "B7") (pin "A'") (pinfunction "P1_A'") (pintype "passive"))
    )
    (net (code "291") (name "unconnected-(B7-S1-PadB')") (class "Default")
      (node (ref "B7") (pin "B'") (pinfunction "S1_B'") (pintype "passive"))
    )
    (net (code "292") (name "unconnected-(B8-P1-PadA')") (class "Default")
      (node (ref "B8") (pin "A'") (pinfunction "P1_A'") (pintype "passive"))
    )
    (net (code "293") (name "unconnected-(B8-S1-PadB')") (class "Default")
      (node (ref "B8") (pin "B'") (pinfunction "S1_B'") (pintype "passive"))
    )
    (net (code "294") (name "unconnected-(B9-P1-PadA')") (class "Default")
      (node (ref "B9") (pin "A'") (pinfunction "P1_A'") (pintype "passive"))
    )
    (net (code "295") (name "unconnected-(B9-S1-PadB')") (class "Default")
      (node (ref "B9") (pin "B'") (pinfunction "S1_B'") (pintype "passive"))
    )
    (net (code "296") (name "unconnected-(B10-P1-PadA')") (class "Default")
      (node (ref "B10") (pin "A'") (pinfunction "P1_A'") (pintype "passive"))
    )
    (net (code "297") (name "unconnected-(B10-S1-PadB')") (class "Default")
      (node (ref "B10") (pin "B'") (pinfunction "S1_B'") (pintype "passive"))
    )
    (net (code "298") (name "unconnected-(B11-P1-PadA')") (class "Default")
      (node (ref "B11") (pin "A'") (pinfunction "P1_A'") (pintype "passive"))
    )
    (net (code "299") (name "unconnected-(B11-S1-PadB')") (class "Default")
      (node (ref "B11") (pin "B'") (pinfunction "S1_B'") (pintype "passive"))
    )
    (net (code "300") (name "unconnected-(B12-P1-PadA')") (class "Default")
      (node (ref "B12") (pin "A'") (pinfunction "P1_A'") (pintype "passive"))
    )
    (net (code "301") (name "unconnected-(B12-S1-PadB')") (class "Default")
      (node (ref "B12") (pin "B'") (pinfunction "S1_B'") (pintype "passive"))
    )
    (net (code "302") (name "unconnected-(B13-P1-PadA')") (class "Default")
      (node (ref "B13") (pin "A'") (pinfunction "P1_A'") (pintype "passive"))
    )
    (net (code "303") (name "unconnected-(B13-S1-PadB')") (class "Default")
      (node (ref "B13") (pin "B'") (pinfunction "S1_B'") (pintype "passive"))
    )
    (net (code "304") (name "unconnected-(B14-P1-PadA')") (class "Default")
      (node (ref "B14") (pin "A'") (pinfunction "P1_A'") (pintype "passive"))
    )
    (net (code "305") (name "unconnected-(B14-S1-PadB')") (class "Default")
      (node (ref "B14") (pin "B'") (pinfunction "S1_B'") (pintype "passive"))
    )
    (net (code "306") (name "unconnected-(B15-P1-PadA')") (class "Default")
      (node (ref "B15") (pin "A'") (pinfunction "P1_A'") (pintype "passive"))
    )
    (net (code "307") (name "unconnected-(B15-S1-PadB')") (class "Default")
      (node (ref "B15") (pin "B'") (pinfunction "S1_B'") (pintype "passive"))
    )
    (net (code "308") (name "unconnected-(B16-P1-PadA')") (class "Default")
      (node (ref "B16") (pin "A'") (pinfunction "P1_A'") (pintype "passive"))
    )
    (net (code "309") (name "unconnected-(B16-S1-PadB')") (class "Default")
      (node (ref "B16") (pin "B'") (pinfunction "S1_B'") (pintype "passive"))
    )
    (net (code "310") (name "unconnected-(B18-P1-PadA')") (class "Default")
      (node (ref "B18") (pin "A'") (pinfunction "P1_A'") (pintype "passive"))
    )
    (net (code "311") (name "unconnected-(B18-S1-PadB')") (class "Default")
      (node (ref "B18") (pin "B'") (pinfunction "S1_B'") (pintype "passive"))
    )
    (net (code "312") (name "unconnected-(B19-P1-PadA')") (class "Default")
      (node (ref "B19") (pin "A'") (pinfunction "P1_A'") (pintype "passive"))
    )
    (net (code "313") (name "unconnected-(B19-S1-PadB')") (class "Default")
      (node (ref "B19") (pin "B'") (pinfunction "S1_B'") (pintype "passive"))
    )
    (net (code "314") (name "unconnected-(B20-P1-PadA')") (class "Default")
      (node (ref "B20") (pin "A'") (pinfunction "P1_A'") (pintype "passive"))
    )
    (net (code "315") (name "unconnected-(B20-S1-PadB')") (class "Default")
      (node (ref "B20") (pin "B'") (pinfunction "S1_B'") (pintype "passive"))
    )
    (net (code "316") (name "unconnected-(B21-P1-PadA')") (class "Default")
      (node (ref "B21") (pin "A'") (pinfunction "P1_A'") (pintype "passive"))
    )
    (net (code "317") (name "unconnected-(B21-S1-PadB')") (class "Default")
      (node (ref "B21") (pin "B'") (pinfunction "S1_B'") (pintype "passive"))
    )
    (net (code "318") (name "unconnected-(B22-P1-PadA')") (class "Default")
      (node (ref "B22") (pin "A'") (pinfunction "P1_A'") (pintype "passive"))
    )
    (net (code "319") (name "unconnected-(B22-S1-PadB')") (class "Default")
      (node (ref "B22") (pin "B'") (pinfunction "S1_B'") (pintype "passive"))
    )
    (net (code "320") (name "unconnected-(B23-P1-PadA')") (class "Default")
      (node (ref "B23") (pin "A'") (pinfunction "P1_A'") (pintype "passive"))
    )
    (net (code "321") (name "unconnected-(B23-S1-PadB')") (class "Default")
      (node (ref "B23") (pin "B'") (pinfunction "S1_B'") (pintype "passive"))
    )
    (net (code "322") (name "unconnected-(B24-P1-PadA')") (class "Default")
      (node (ref "B24") (pin "A'") (pinfunction "P1_A'") (pintype "passive"))
    )
    (net (code "323") (name "unconnected-(B24-S1-PadB')") (class "Default")
      (node (ref "B24") (pin "B'") (pinfunction "S1_B'") (pintype "passive"))
    )
    (net (code "324") (name "unconnected-(B25-P1-PadA')") (class "Default")
      (node (ref "B25") (pin "A'") (pinfunction "P1_A'") (pintype "passive"))
    )
    (net (code "325") (name "unconnected-(B25-S1-PadB')") (class "Default")
      (node (ref "B25") (pin "B'") (pinfunction "S1_B'") (pintype "passive"))
    )
    (net (code "326") (name "unconnected-(B26-P1-PadA')") (class "Default")
      (node (ref "B26") (pin "A'") (pinfunction "P1_A'") (pintype "passive"))
    )
    (net (code "327") (name "unconnected-(B26-S1-PadB')") (class "Default")
      (node (ref "B26") (pin "B'") (pinfunction "S1_B'") (pintype "passive"))
    )
    (net (code "328") (name "unconnected-(B27-P1-PadA')") (class "Default")
      (node (ref "B27") (pin "A'") (pinfunction "P1_A'") (pintype "passive"))
    )
    (net (code "329") (name "unconnected-(B27-S1-PadB')") (class "Default")
      (node (ref "B27") (pin "B'") (pinfunction "S1_B'") (pintype "passive"))
    )
    (net (code "330") (name "unconnected-(B28-P1-PadA')") (class "Default")
      (node (ref "B28") (pin "A'") (pinfunction "P1_A'") (pintype "passive"))
    )
    (net (code "331") (name "unconnected-(B28-S1-PadB')") (class "Default")
      (node (ref "B28") (pin "B'") (pinfunction "S1_B'") (pintype "passive"))
    )
    (net (code "332") (name "unconnected-(B29-P1-PadA')") (class "Default")
      (node (ref "B29") (pin "A'") (pinfunction "P1_A'") (pintype "passive"))
    )
    (net (code "333") (name "unconnected-(B29-S1-PadB')") (class "Default")
      (node (ref "B29") (pin "B'") (pinfunction "S1_B'") (pintype "passive"))
    )
    (net (code "334") (name "unconnected-(B30-P1-PadA')") (class "Default")
      (node (ref "B30") (pin "A'") (pinfunction "P1_A'") (pintype "passive"))
    )
    (net (code "335") (name "unconnected-(B30-S1-PadB')") (class "Default")
      (node (ref "B30") (pin "B'") (pinfunction "S1_B'") (pintype "passive"))
    )
    (net (code "336") (name "unconnected-(B31-P1-PadA')") (class "Default")
      (node (ref "B31") (pin "A'") (pinfunction "P1_A'") (pintype "passive"))
    )
    (net (code "337") (name "unconnected-(B31-S1-PadB')") (class "Default")
      (node (ref "B31") (pin "B'") (pinfunction "S1_B'") (pintype "passive"))
    )
    (net (code "338") (name "unconnected-(B32-P1-PadA')") (class "Default")
      (node (ref "B32") (pin "A'") (pinfunction "P1_A'") (pintype "passive"))
    )
    (net (code "339") (name "unconnected-(B32-S1-PadB')") (class "Default")
      (node (ref "B32") (pin "B'") (pinfunction "S1_B'") (pintype "passive"))
    )
    (net (code "340") (name "unconnected-(B33-P1-PadA')") (class "Default")
      (node (ref "B33") (pin "A'") (pinfunction "P1_A'") (pintype "passive"))
    )
    (net (code "341") (name "unconnected-(B33-S1-PadB')") (class "Default")
      (node (ref "B33") (pin "B'") (pinfunction "S1_B'") (pintype "passive"))
    )
    (net (code "342") (name "unconnected-(B34-P1-PadA')") (class "Default")
      (node (ref "B34") (pin "A'") (pinfunction "P1_A'") (pintype "passive"))
    )
    (net (code "343") (name "unconnected-(B34-S1-PadB')") (class "Default")
      (node (ref "B34") (pin "B'") (pinfunction "S1_B'") (pintype "passive"))
    )
    (net (code "344") (name "unconnected-(B35-P1-PadA')") (class "Default")
      (node (ref "B35") (pin "A'") (pinfunction "P1_A'") (pintype "passive"))
    )
    (net (code "345") (name "unconnected-(B35-S1-PadB')") (class "Default")
      (node (ref "B35") (pin "B'") (pinfunction "S1_B'") (pintype "passive"))
    )
    (net (code "346") (name "unconnected-(B36-P1-PadA')") (class "Default")
      (node (ref "B36") (pin "A'") (pinfunction "P1_A'") (pintype "passive"))
    )
    (net (code "347") (name "unconnected-(B36-S1-PadB')") (class "Default")
      (node (ref "B36") (pin "B'") (pinfunction "S1_B'") (pintype "passive"))
    )
    (net (code "348") (name "unconnected-(B38-P1-PadA')") (class "Default")
      (node (ref "B38") (pin "A'") (pinfunction "P1_A'") (pintype "passive"))
    )
    (net (code "349") (name "unconnected-(B38-S1-PadB')") (class "Default")
      (node (ref "B38") (pin "B'") (pinfunction "S1_B'") (pintype "passive"))
    )
    (net (code "350") (name "unconnected-(B39-P1-PadA')") (class "Default")
      (node (ref "B39") (pin "A'") (pinfunction "P1_A'") (pintype "passive"))
    )
    (net (code "351") (name "unconnected-(B39-S1-PadB')") (class "Default")
      (node (ref "B39") (pin "B'") (pinfunction "S1_B'") (pintype "passive"))
    )
    (net (code "352") (name "unconnected-(B40-P1-PadA')") (class "Default")
      (node (ref "B40") (pin "A'") (pinfunction "P1_A'") (pintype "passive"))
    )
    (net (code "353") (name "unconnected-(B40-S1-PadB')") (class "Default")
      (node (ref "B40") (pin "B'") (pinfunction "S1_B'") (pintype "passive"))
    )
    (net (code "354") (name "unconnected-(B41-P1-PadA')") (class "Default")
      (node (ref "B41") (pin "A'") (pinfunction "P1_A'") (pintype "passive"))
    )
    (net (code "355") (name "unconnected-(B41-S1-PadB')") (class "Default")
      (node (ref "B41") (pin "B'") (pinfunction "S1_B'") (pintype "passive"))
    )
    (net (code "356") (name "unconnected-(B42-P1-PadA')") (class "Default")
      (node (ref "B42") (pin "A'") (pinfunction "P1_A'") (pintype "passive"))
    )
    (net (code "357") (name "unconnected-(B42-S1-PadB')") (class "Default")
      (node (ref "B42") (pin "B'") (pinfunction "S1_B'") (pintype "passive"))
    )
    (net (code "358") (name "unconnected-(B43-P1-PadA')") (class "Default")
      (node (ref "B43") (pin "A'") (pinfunction "P1_A'") (pintype "passive"))
    )
    (net (code "359") (name "unconnected-(B43-S1-PadB')") (class "Default")
      (node (ref "B43") (pin "B'") (pinfunction "S1_B'") (pintype "passive"))
    )
    (net (code "360") (name "unconnected-(B44-P1-PadA')") (class "Default")
      (node (ref "B44") (pin "A'") (pinfunction "P1_A'") (pintype "passive"))
    )
    (net (code "361") (name "unconnected-(B44-S1-PadB')") (class "Default")
      (node (ref "B44") (pin "B'") (pinfunction "S1_B'") (pintype "passive"))
    )
    (net (code "362") (name "unconnected-(B45-P1-PadA')") (class "Default")
      (node (ref "B45") (pin "A'") (pinfunction "P1_A'") (pintype "passive"))
    )
    (net (code "363") (name "unconnected-(B45-S1-PadB')") (class "Default")
      (node (ref "B45") (pin "B'") (pinfunction "S1_B'") (pintype "passive"))
    )
    (net (code "364") (name "unconnected-(B46-P1-PadA')") (class "Default")
      (node (ref "B46") (pin "A'") (pinfunction "P1_A'") (pintype "passive"))
    )
    (net (code "365") (name "unconnected-(B46-S1-PadB')") (class "Default")
      (node (ref "B46") (pin "B'") (pinfunction "S1_B'") (pintype "passive"))
    )
    (net (code "366") (name "unconnected-(B47-P1-PadA')") (class "Default")
      (node (ref "B47") (pin "A'") (pinfunction "P1_A'") (pintype "passive"))
    )
    (net (code "367") (name "unconnected-(B47-S1-PadB')") (class "Default")
      (node (ref "B47") (pin "B'") (pinfunction "S1_B'") (pintype "passive"))
    )
    (net (code "368") (name "unconnected-(B48-P1-PadA')") (class "Default")
      (node (ref "B48") (pin "A'") (pinfunction "P1_A'") (pintype "passive"))
    )
    (net (code "369") (name "unconnected-(B48-S1-PadB')") (class "Default")
      (node (ref "B48") (pin "B'") (pinfunction "S1_B'") (pintype "passive"))
    )
    (net (code "370") (name "unconnected-(B49-P1-PadA')") (class "Default")
      (node (ref "B49") (pin "A'") (pinfunction "P1_A'") (pintype "passive"))
    )
    (net (code "371") (name "unconnected-(B49-S1-PadB')") (class "Default")
      (node (ref "B49") (pin "B'") (pinfunction "S1_B'") (pintype "passive"))
    )
    (net (code "372") (name "unconnected-(B50-P1-PadA')") (class "Default")
      (node (ref "B50") (pin "A'") (pinfunction "P1_A'") (pintype "passive"))
    )
    (net (code "373") (name "unconnected-(B50-S1-PadB')") (class "Default")
      (node (ref "B50") (pin "B'") (pinfunction "S1_B'") (pintype "passive"))
    )
    (net (code "374") (name "unconnected-(B51-P1-PadA')") (class "Default")
      (node (ref "B51") (pin "A'") (pinfunction "P1_A'") (pintype "passive"))
    )
    (net (code "375") (name "unconnected-(B51-S1-PadB')") (class "Default")
      (node (ref "B51") (pin "B'") (pinfunction "S1_B'") (pintype "passive"))
    )
    (net (code "376") (name "unconnected-(B52-P1-PadA')") (class "Default")
      (node (ref "B52") (pin "A'") (pinfunction "P1_A'") (pintype "passive"))
    )
    (net (code "377") (name "unconnected-(B52-S1-PadB')") (class "Default")
      (node (ref "B52") (pin "B'") (pinfunction "S1_B'") (pintype "passive"))
    )
    (net (code "378") (name "unconnected-(B53-P1-PadA')") (class "Default")
      (node (ref "B53") (pin "A'") (pinfunction "P1_A'") (pintype "passive"))
    )
    (net (code "379") (name "unconnected-(B53-S1-PadB')") (class "Default")
      (node (ref "B53") (pin "B'") (pinfunction "S1_B'") (pintype "passive"))
    )
    (net (code "380") (name "unconnected-(B54-P1-PadA')") (class "Default")
      (node (ref "B54") (pin "A'") (pinfunction "P1_A'") (pintype "passive"))
    )
    (net (code "381") (name "unconnected-(B54-S1-PadB')") (class "Default")
      (node (ref "B54") (pin "B'") (pinfunction "S1_B'") (pintype "passive"))
    )
    (net (code "382") (name "unconnected-(B55-P1-PadA')") (class "Default")
      (node (ref "B55") (pin "A'") (pinfunction "P1_A'") (pintype "passive"))
    )
    (net (code "383") (name "unconnected-(B55-S1-PadB')") (class "Default")
      (node (ref "B55") (pin "B'") (pinfunction "S1_B'") (pintype "passive"))
    )
    (net (code "384") (name "unconnected-(B56-P1-PadA')") (class "Default")
      (node (ref "B56") (pin "A'") (pinfunction "P1_A'") (pintype "passive"))
    )
    (net (code "385") (name "unconnected-(B56-S1-PadB')") (class "Default")
      (node (ref "B56") (pin "B'") (pinfunction "S1_B'") (pintype "passive"))
    )
    (net (code "386") (name "unconnected-(B57-P1-PadA')") (class "Default")
      (node (ref "B57") (pin "A'") (pinfunction "P1_A'") (pintype "passive"))
    )
    (net (code "387") (name "unconnected-(B57-S1-PadB')") (class "Default")
      (node (ref "B57") (pin "B'") (pinfunction "S1_B'") (pintype "passive"))
    )
    (net (code "388") (name "unconnected-(B58-P1-PadA')") (class "Default")
      (node (ref "B58") (pin "A'") (pinfunction "P1_A'") (pintype "passive"))
    )
    (net (code "389") (name "unconnected-(B58-S1-PadB')") (class "Default")
      (node (ref "B58") (pin "B'") (pinfunction "S1_B'") (pintype "passive"))
    )
    (net (code "390") (name "unconnected-(B59-P1-PadA')") (class "Default")
      (node (ref "B59") (pin "A'") (pinfunction "P1_A'") (pintype "passive"))
    )
    (net (code "391") (name "unconnected-(B59-S1-PadB')") (class "Default")
      (node (ref "B59") (pin "B'") (pinfunction "S1_B'") (pintype "passive"))
    )
    (net (code "392") (name "unconnected-(B60-P1-PadA')") (class "Default")
      (node (ref "B60") (pin "A'") (pinfunction "P1_A'") (pintype "passive"))
    )
    (net (code "393") (name "unconnected-(B60-S1-PadB')") (class "Default")
      (node (ref "B60") (pin "B'") (pinfunction "S1_B'") (pintype "passive"))
    )
    (net (code "394") (name "unconnected-(JP1-Pad3)") (class "Default")
      (node (ref "JP1") (pin "3") (pinfunction "3_3") (pintype "passive"))
    )
    (net (code "395") (name "unconnected-(N37-P1-PadA')") (class "Default")
      (node (ref "N37") (pin "A'") (pinfunction "P1_A'") (pintype "passive"))
    )
    (net (code "396") (name "unconnected-(N37-S1-PadB')") (class "Default")
      (node (ref "N37") (pin "B'") (pinfunction "S1_B'") (pintype "passive"))
    )
    (net (code "397") (name "unconnected-(TFT1-DE-Pad14)") (class "Default")
      (node (ref "TFT1") (pin "14") (pinfunction "DE_14") (pintype "bidirectional"))
    )
    (net (code "398") (name "unconnected-(TFT1-DOTCLK-Pad13)") (class "Default")
      (node (ref "TFT1") (pin "13") (pinfunction "DOTCLK_13") (pintype "bidirectional"))
    )
    (net (code "399") (name "unconnected-(TFT1-HSYNC-Pad12)") (class "Default")
      (node (ref "TFT1") (pin "12") (pinfunction "HSYNC_12") (pintype "bidirectional"))
    )
    (net (code "400") (name "unconnected-(TFT1-TE-Pad39)") (class "Default")
      (node (ref "TFT1") (pin "39") (pinfunction "TE_39") (pintype "bidirectional"))
    )
    (net (code "401") (name "unconnected-(TFT1-VSYNC-Pad11)") (class "Default")
      (node (ref "TFT1") (pin "11") (pinfunction "VSYNC_11") (pintype "bidirectional"))
    )
    (net (code "402") (name "unconnected-(TFT1-{slash}RD-Pad35)") (class "Default")
      (node (ref "TFT1") (pin "35") (pinfunction "/RD_35") (pintype "bidirectional"))
    )
    (net (code "403") (name "unconnected-(U1-ADJ-Pad4)") (class "Default")
      (node (ref "U1") (pin "4") (pinfunction "ADJ_4") (pintype "bidirectional"))
    )
    (net (code "404") (name "unconnected-(U2-NC1-Pad5)") (class "Default")
      (node (ref "U2") (pin "5") (pinfunction "NC1_5") (pintype "bidirectional"))
    )
    (net (code "405") (name "unconnected-(U2-NC2-Pad11)") (class "Default")
      (node (ref "U2") (pin "11") (pinfunction "NC2_11") (pintype "bidirectional"))
    )
    (net (code "406") (name "unconnected-(UTSC-IN0{slash}GPIO-0-Pad8)") (class "Default")
      (node (ref "UTSC") (pin "8") (pinfunction "IN0/GPIO-0_8") (pintype "bidirectional"))
    )
    (net (code "407") (name "unconnected-(UTSC-IN3{slash}GPIO-3-Pad12)") (class "Default")
      (node (ref "UTSC") (pin "12") (pinfunction "IN3/GPIO-3_12") (pintype "bidirectional"))
    )
  )
)
